# PCB_ROHM_BaAnh.net
KiCad netlist of a schematic drawn in EAGLE
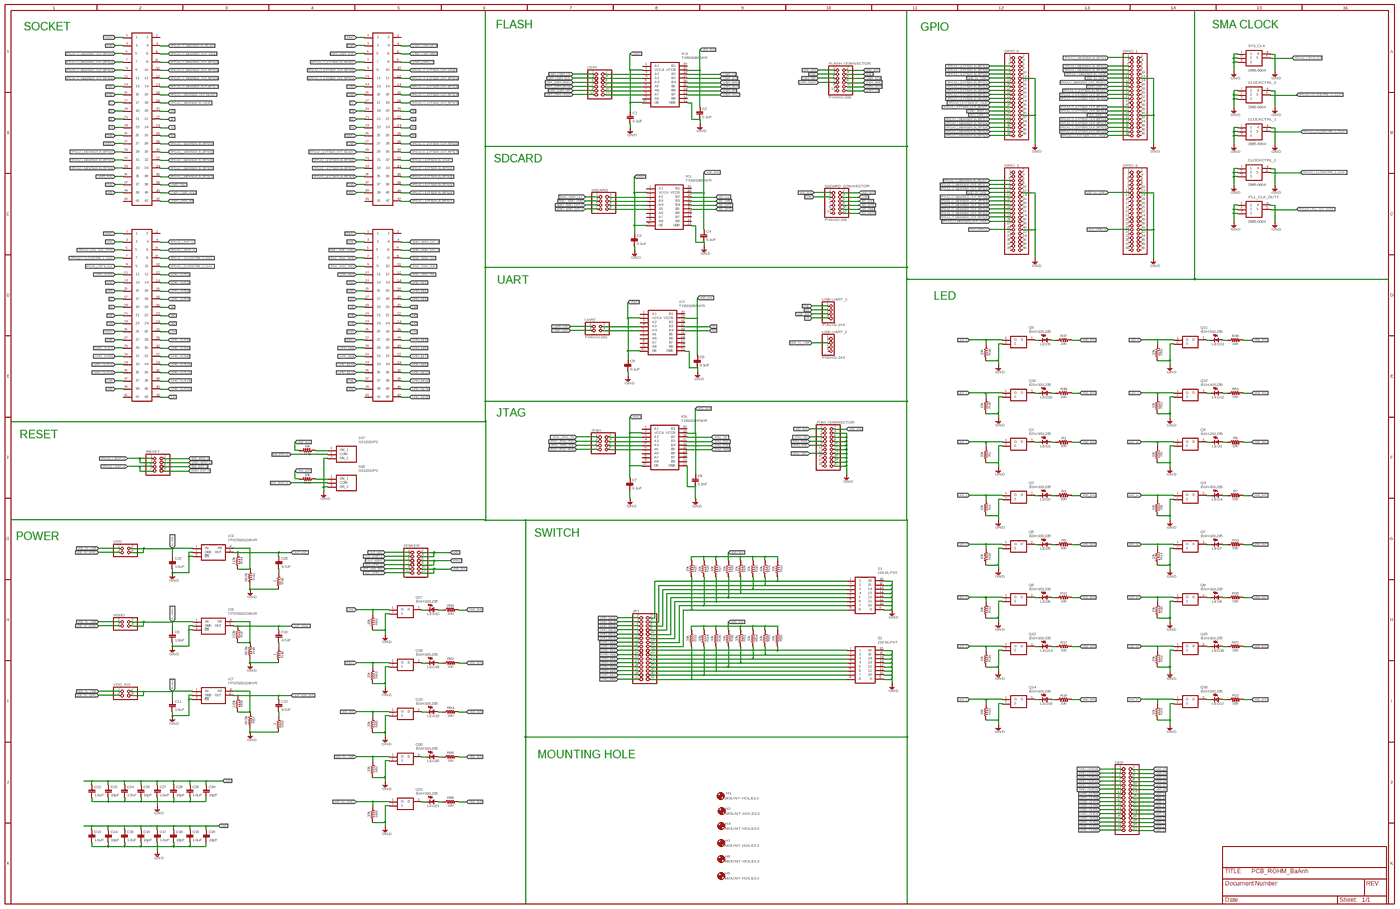
[diagram p0: schematic, sheet 1, overview]
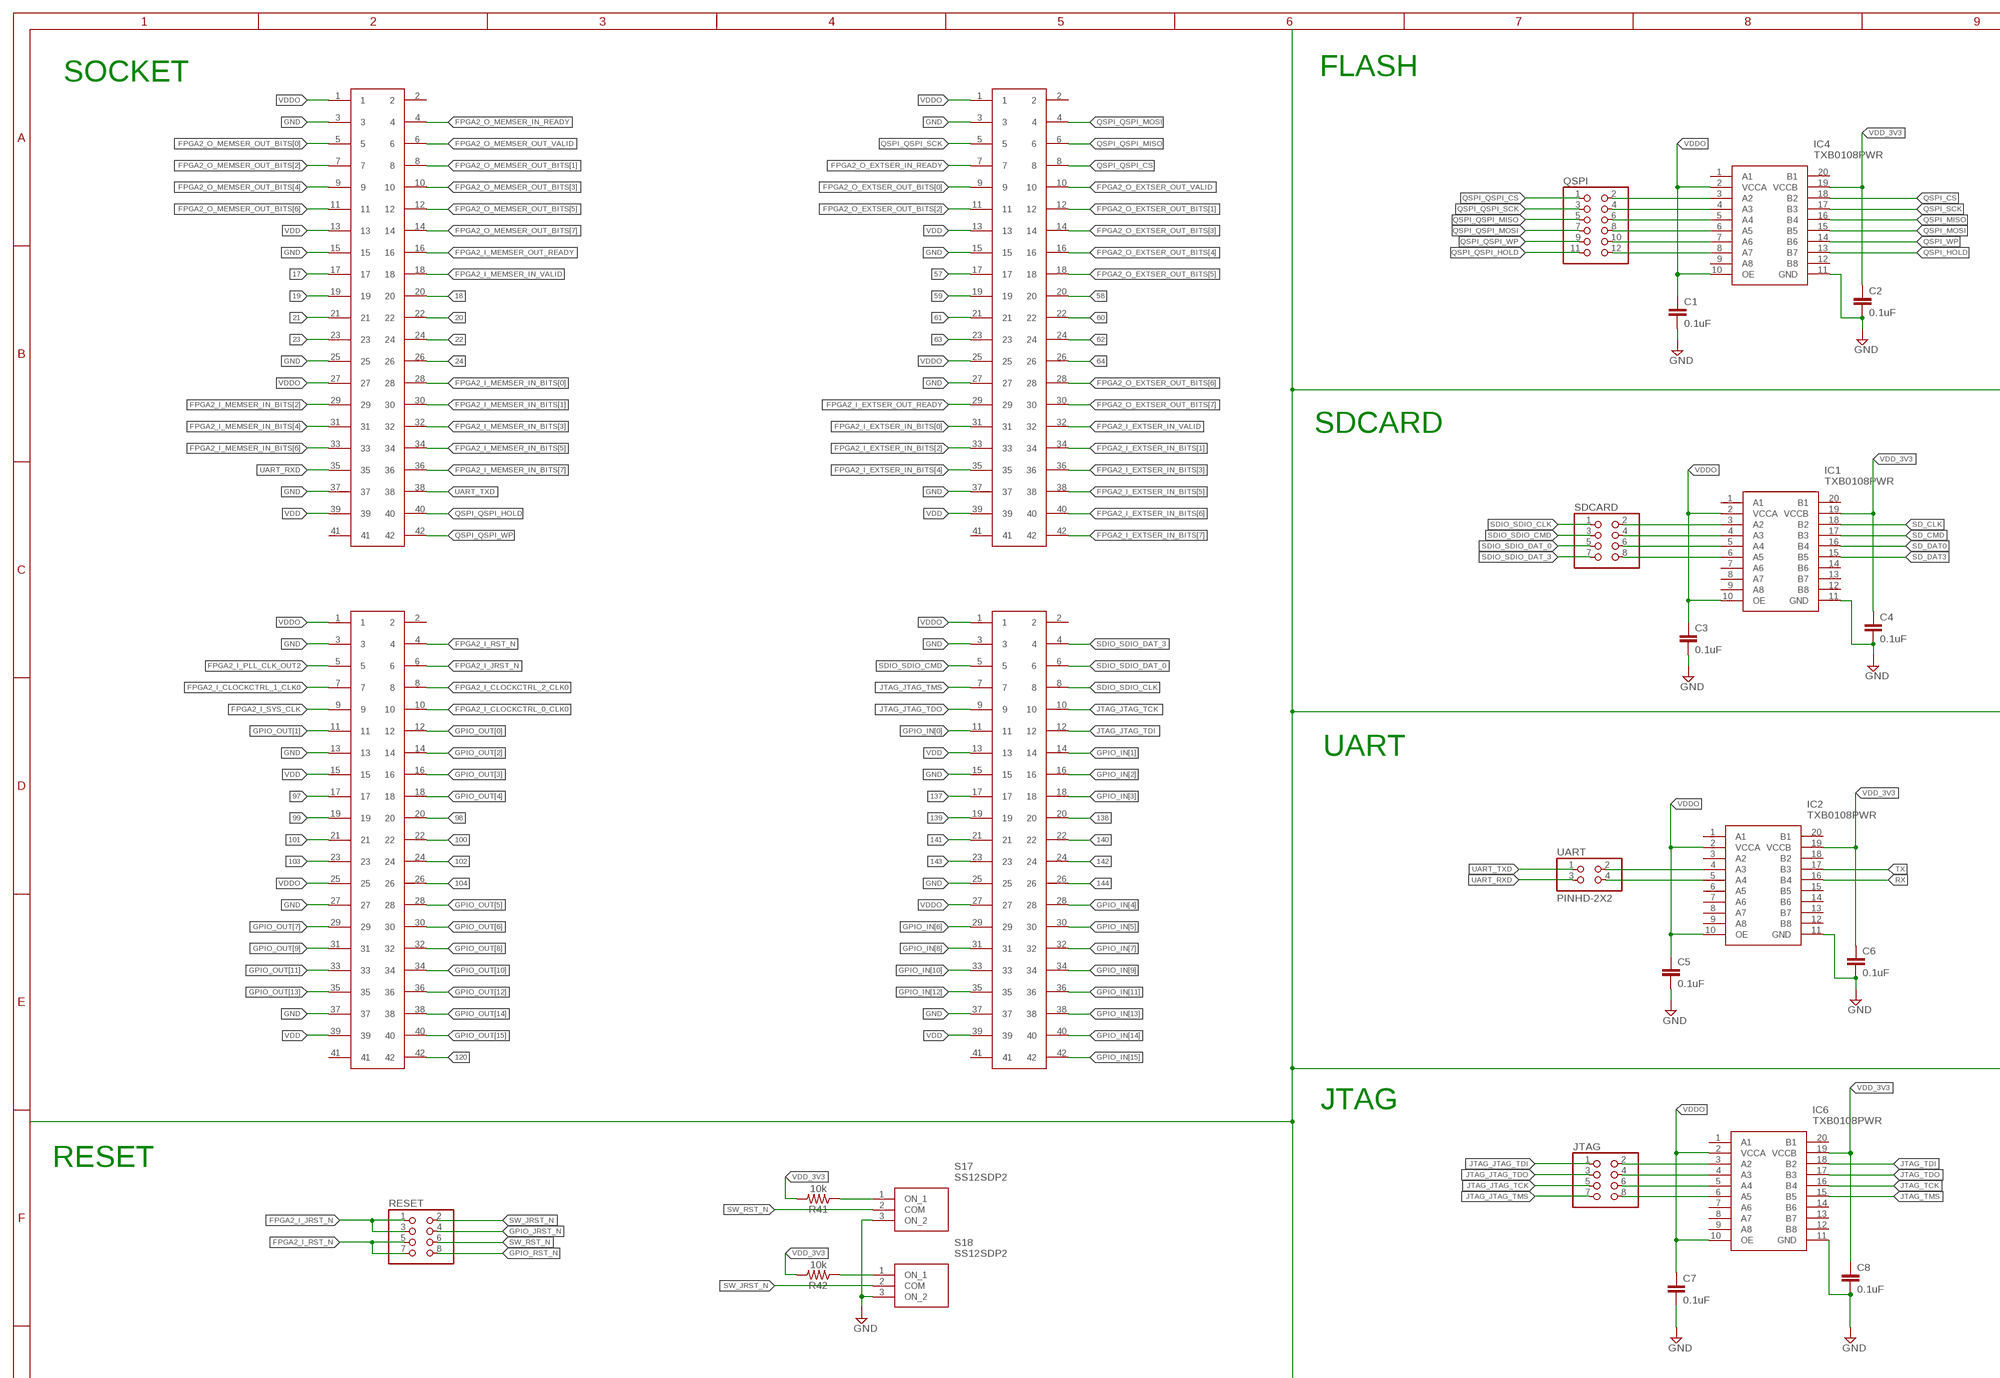
[diagram p1: schematic, sheet 1, part 1 of 4]
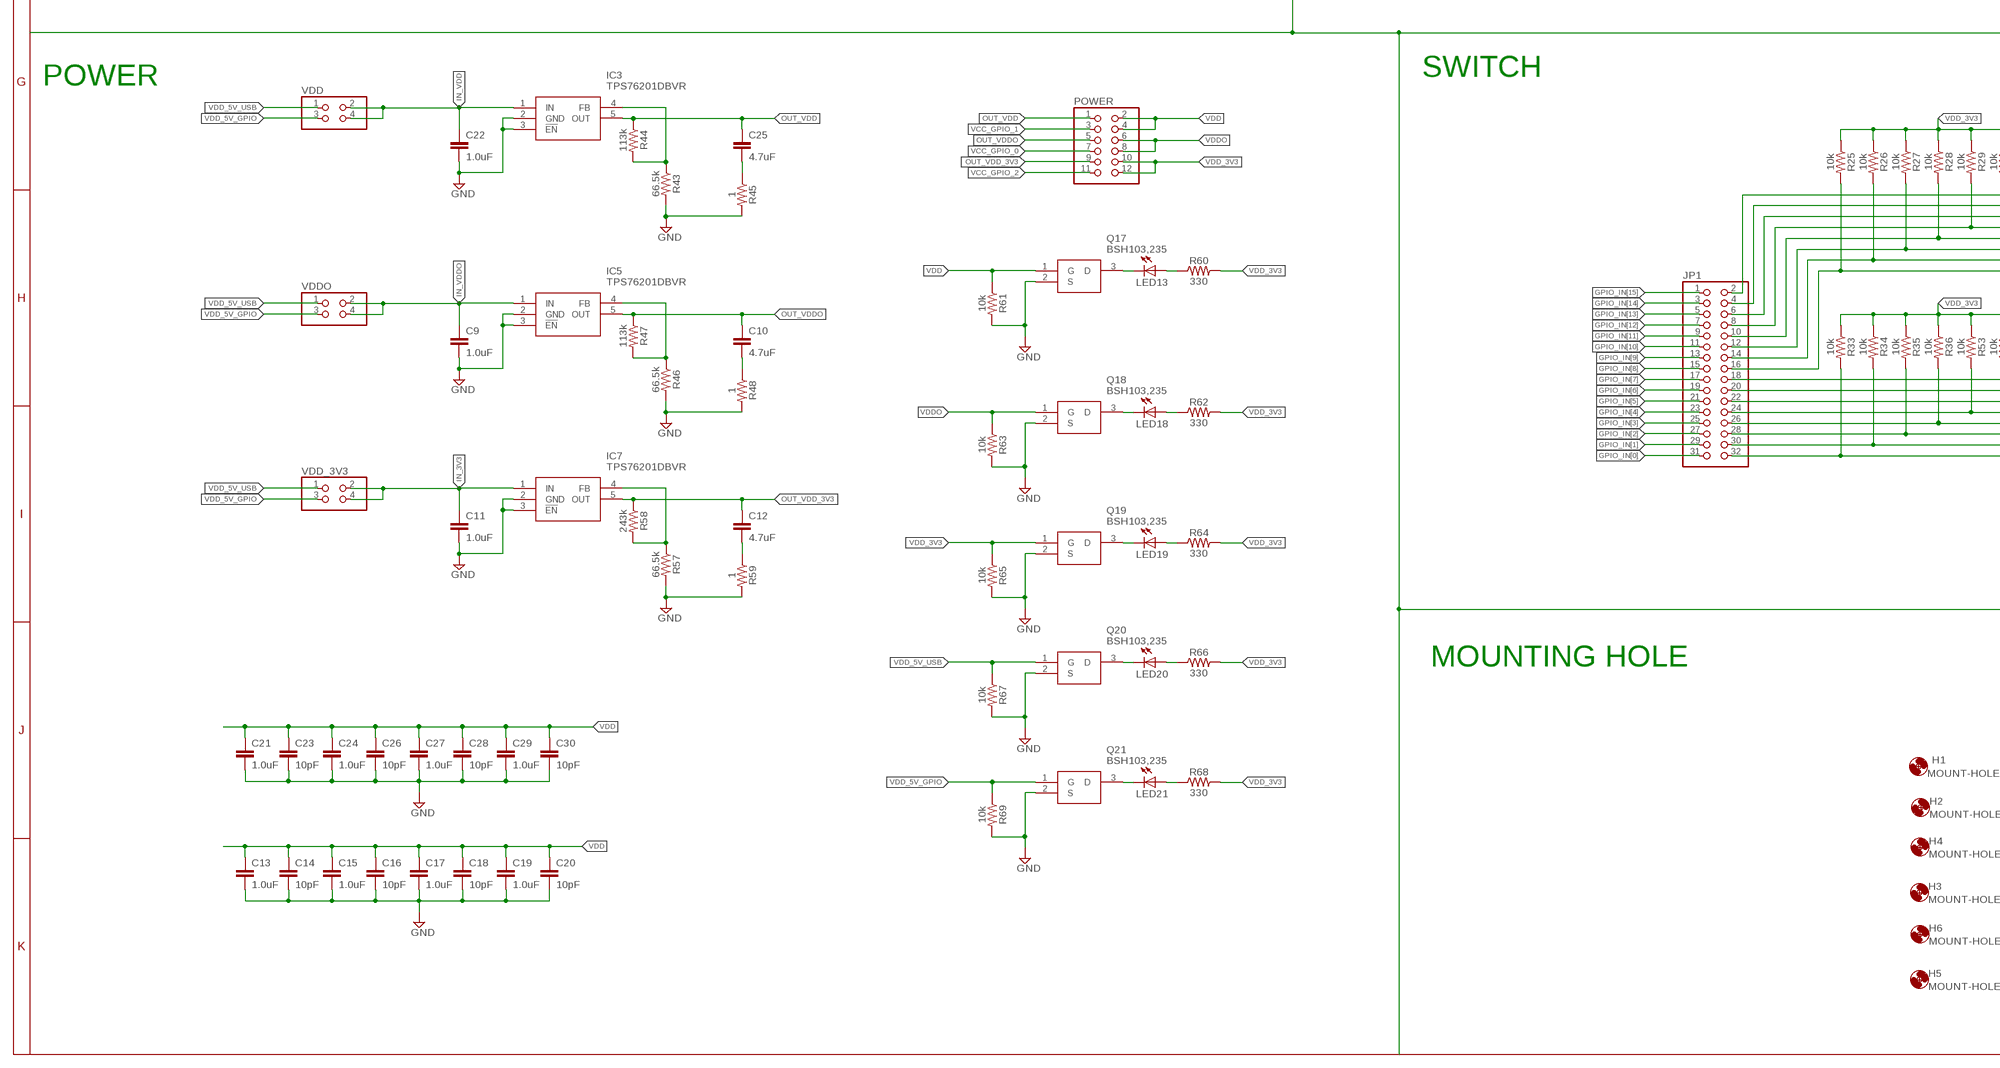
[diagram p2: schematic, sheet 1, part 2 of 4]
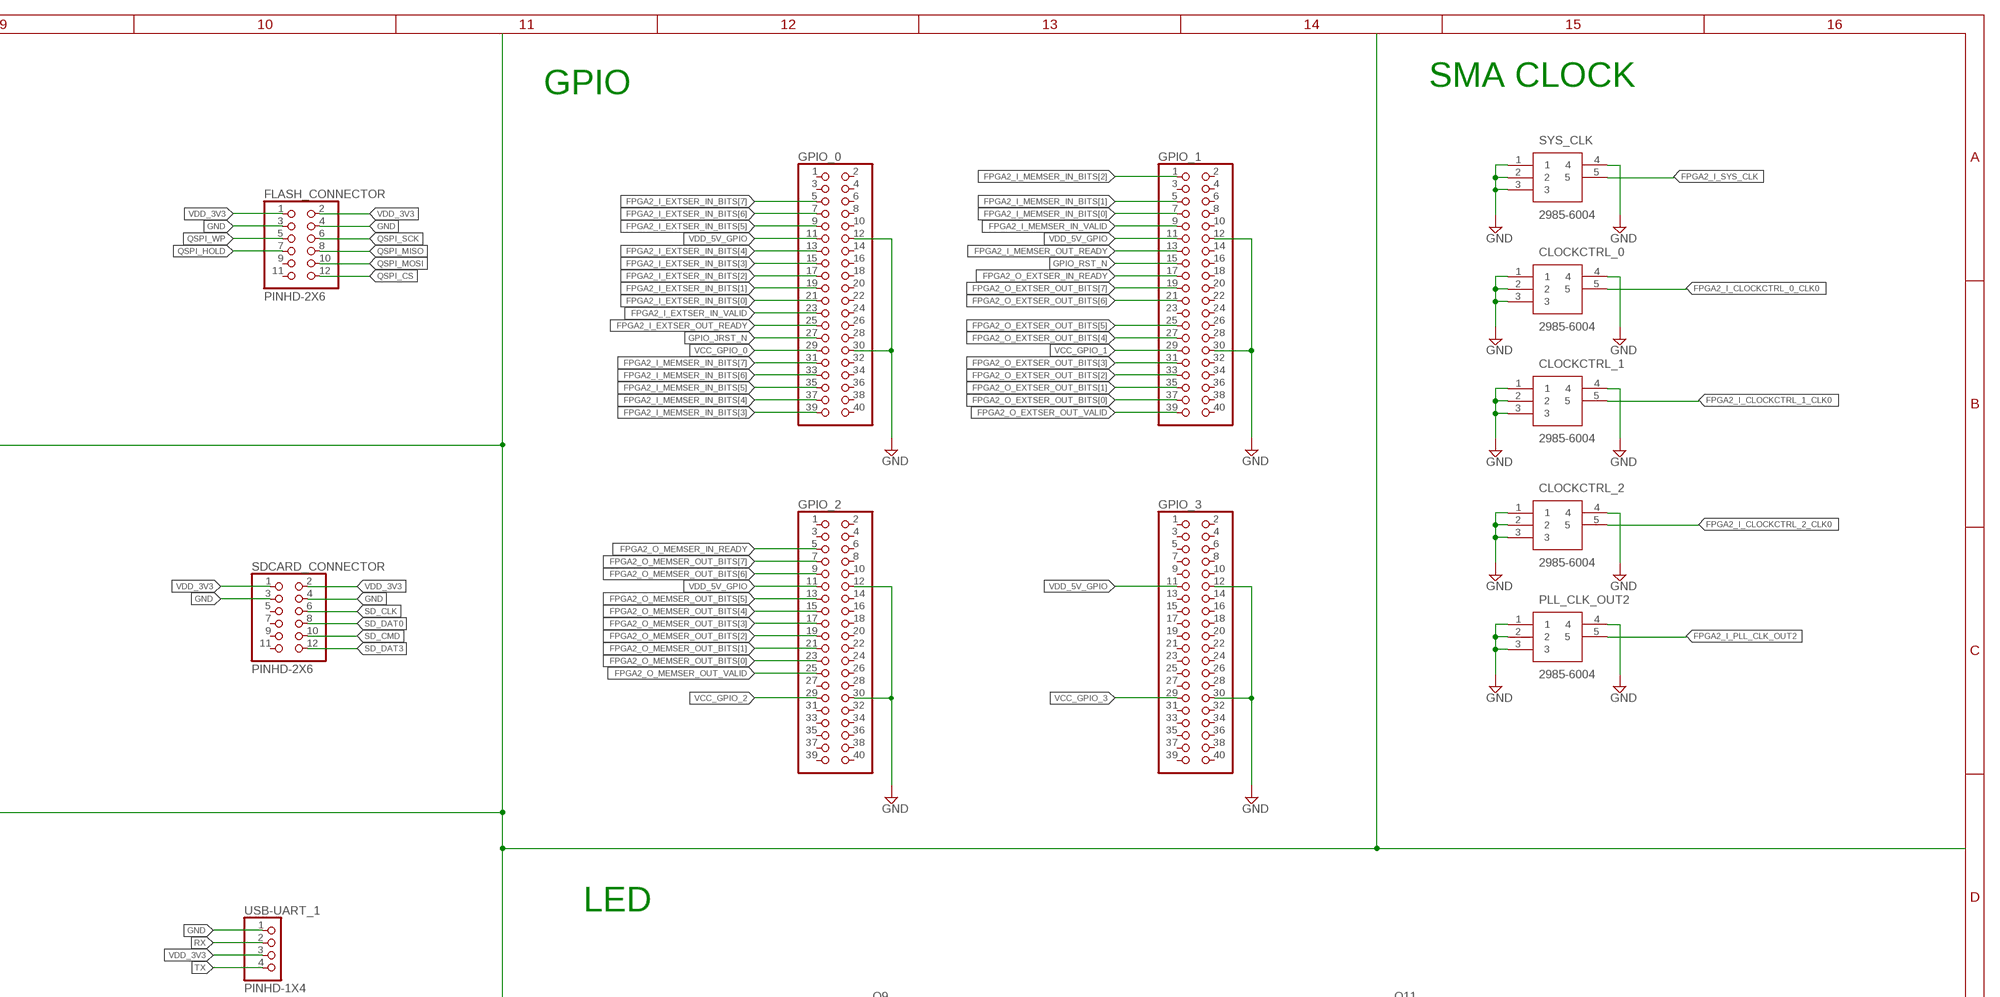
[diagram p3: schematic, sheet 1, part 3 of 4]
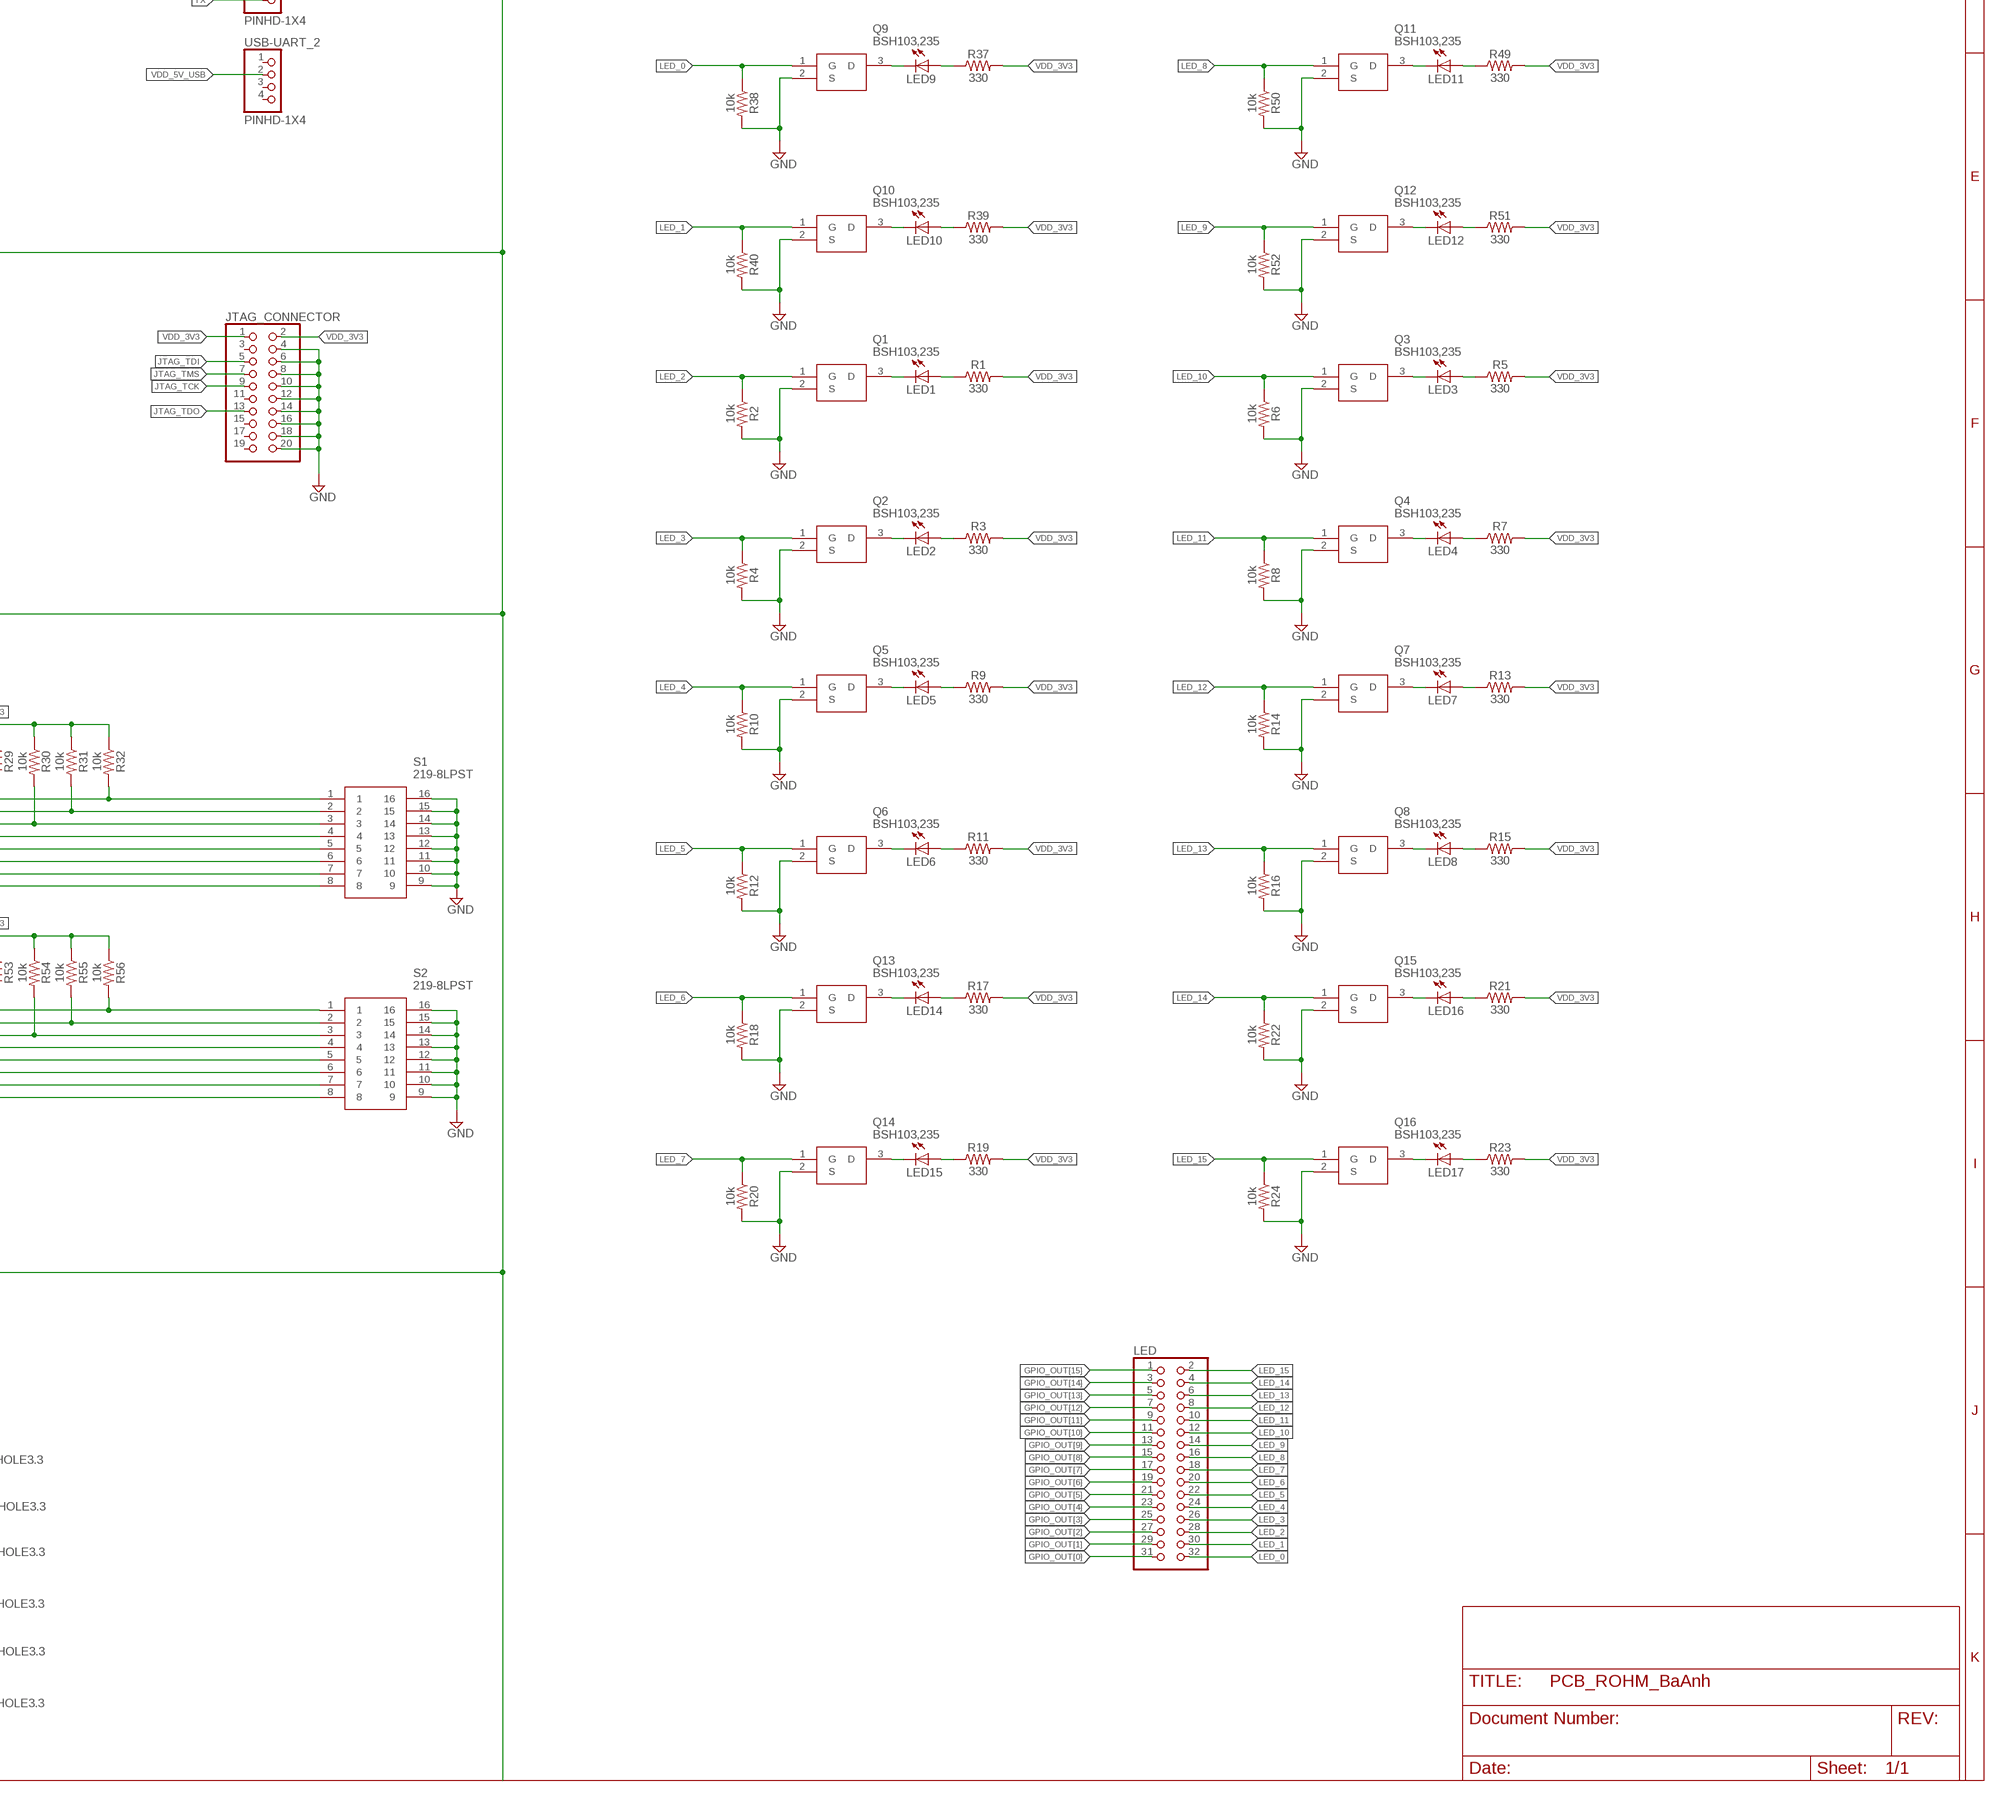
[diagram p4: schematic, sheet 1, part 4 of 4]

(export (version "E")
  (design (tool "Eeschema 10.0.6"))
  (components
    (comp (ref "C1")
      (value "0.1uF")
      (footprint "eagle-import:0805")
      (libsource (lib "eagle-import") (part "1.0UF-0805-25V-(+80/-20%)"))
    )
    (comp (ref "C2")
      (value "0.1uF")
      (footprint "eagle-import:0805")
      (libsource (lib "eagle-import") (part "1.0UF-0805-25V-(+80/-20%)"))
    )
    (comp (ref "C3")
      (value "0.1uF")
      (footprint "eagle-import:0805")
      (libsource (lib "eagle-import") (part "1.0UF-0805-25V-(+80/-20%)"))
    )
    (comp (ref "C4")
      (value "0.1uF")
      (footprint "eagle-import:0805")
      (libsource (lib "eagle-import") (part "1.0UF-0805-25V-(+80/-20%)"))
    )
    (comp (ref "C5")
      (value "0.1uF")
      (footprint "eagle-import:0805")
      (libsource (lib "eagle-import") (part "1.0UF-0805-25V-(+80/-20%)"))
    )
    (comp (ref "C6")
      (value "0.1uF")
      (footprint "eagle-import:0805")
      (libsource (lib "eagle-import") (part "1.0UF-0805-25V-(+80/-20%)"))
    )
    (comp (ref "C7")
      (value "0.1uF")
      (footprint "eagle-import:0805")
      (libsource (lib "eagle-import") (part "1.0UF-0805-25V-(+80/-20%)"))
    )
    (comp (ref "C8")
      (value "0.1uF")
      (footprint "eagle-import:0805")
      (libsource (lib "eagle-import") (part "1.0UF-0805-25V-(+80/-20%)"))
    )
    (comp (ref "C9")
      (value "1.0uF")
      (footprint "eagle-import:0805")
      (libsource (lib "eagle-import") (part "1.0UF-0805-25V-(+80/-20%)"))
    )
    (comp (ref "C10")
      (value "4.7uF")
      (footprint "eagle-import:0805")
      (libsource (lib "eagle-import") (part "1.0UF-0805-25V-(+80/-20%)"))
    )
    (comp (ref "C11")
      (value "1.0uF")
      (footprint "eagle-import:0805")
      (libsource (lib "eagle-import") (part "1.0UF-0805-25V-(+80/-20%)"))
    )
    (comp (ref "C12")
      (value "4.7uF")
      (footprint "eagle-import:0805")
      (libsource (lib "eagle-import") (part "1.0UF-0805-25V-(+80/-20%)"))
    )
    (comp (ref "C13")
      (value "1.0uF")
      (footprint "eagle-import:0805")
      (libsource (lib "eagle-import") (part "1.0UF-0805-25V-(+80/-20%)"))
    )
    (comp (ref "C14")
      (value "10pF")
      (footprint "eagle-import:0805")
      (libsource (lib "eagle-import") (part "1.0UF-0805-25V-(+80/-20%)"))
    )
    (comp (ref "C15")
      (value "1.0uF")
      (footprint "eagle-import:0805")
      (libsource (lib "eagle-import") (part "1.0UF-0805-25V-(+80/-20%)"))
    )
    (comp (ref "C16")
      (value "10pF")
      (footprint "eagle-import:0805")
      (libsource (lib "eagle-import") (part "1.0UF-0805-25V-(+80/-20%)"))
    )
    (comp (ref "C17")
      (value "1.0uF")
      (footprint "eagle-import:0805")
      (libsource (lib "eagle-import") (part "1.0UF-0805-25V-(+80/-20%)"))
    )
    (comp (ref "C18")
      (value "10pF")
      (footprint "eagle-import:0805")
      (libsource (lib "eagle-import") (part "1.0UF-0805-25V-(+80/-20%)"))
    )
    (comp (ref "C19")
      (value "1.0uF")
      (footprint "eagle-import:0805")
      (libsource (lib "eagle-import") (part "1.0UF-0805-25V-(+80/-20%)"))
    )
    (comp (ref "C20")
      (value "10pF")
      (footprint "eagle-import:0805")
      (libsource (lib "eagle-import") (part "1.0UF-0805-25V-(+80/-20%)"))
    )
    (comp (ref "C21")
      (value "1.0uF")
      (footprint "eagle-import:0805")
      (libsource (lib "eagle-import") (part "1.0UF-0805-25V-(+80/-20%)"))
    )
    (comp (ref "C22")
      (value "1.0uF")
      (footprint "eagle-import:0805")
      (libsource (lib "eagle-import") (part "1.0UF-0805-25V-(+80/-20%)"))
    )
    (comp (ref "C23")
      (value "10pF")
      (footprint "eagle-import:0805")
      (libsource (lib "eagle-import") (part "1.0UF-0805-25V-(+80/-20%)"))
    )
    (comp (ref "C24")
      (value "1.0uF")
      (footprint "eagle-import:0805")
      (libsource (lib "eagle-import") (part "1.0UF-0805-25V-(+80/-20%)"))
    )
    (comp (ref "C25")
      (value "4.7uF")
      (footprint "eagle-import:0805")
      (libsource (lib "eagle-import") (part "1.0UF-0805-25V-(+80/-20%)"))
    )
    (comp (ref "C26")
      (value "10pF")
      (footprint "eagle-import:0805")
      (libsource (lib "eagle-import") (part "1.0UF-0805-25V-(+80/-20%)"))
    )
    (comp (ref "C27")
      (value "1.0uF")
      (footprint "eagle-import:0805")
      (libsource (lib "eagle-import") (part "1.0UF-0805-25V-(+80/-20%)"))
    )
    (comp (ref "C28")
      (value "10pF")
      (footprint "eagle-import:0805")
      (libsource (lib "eagle-import") (part "1.0UF-0805-25V-(+80/-20%)"))
    )
    (comp (ref "C29")
      (value "1.0uF")
      (footprint "eagle-import:0805")
      (libsource (lib "eagle-import") (part "1.0UF-0805-25V-(+80/-20%)"))
    )
    (comp (ref "C30")
      (value "10pF")
      (footprint "eagle-import:0805")
      (libsource (lib "eagle-import") (part "1.0UF-0805-25V-(+80/-20%)"))
    )
    (comp (ref "CLOCKCTRL_0")
      (value "2985-6004")
      (footprint "eagle-import:29856004")
      (fields (field (name "MOUSER_PART_NUMBER") "523-2985-6004"))
      (libsource (lib "eagle-import") (part "2985-6004"))
    )
    (comp (ref "CLOCKCTRL_1")
      (value "2985-6004")
      (footprint "eagle-import:29856004")
      (fields (field (name "MOUSER_PART_NUMBER") "523-2985-6004"))
      (libsource (lib "eagle-import") (part "2985-6004"))
    )
    (comp (ref "CLOCKCTRL_2")
      (value "2985-6004")
      (footprint "eagle-import:29856004")
      (fields (field (name "MOUSER_PART_NUMBER") "523-2985-6004"))
      (libsource (lib "eagle-import") (part "2985-6004"))
    )
    (comp (ref "FLASH_CONNECTOR")
      (value "PINHD-2X6")
      (footprint "eagle-import:2X06")
      (libsource (lib "eagle-import") (part "PINHD-2X6"))
    )
    (comp (ref "GPIO_0")
      (value "PINHD-2X20")
      (footprint "eagle-import:2X20")
      (libsource (lib "eagle-import") (part "PINHD-2X20"))
    )
    (comp (ref "GPIO_1")
      (value "PINHD-2X20")
      (footprint "eagle-import:2X20")
      (libsource (lib "eagle-import") (part "PINHD-2X20"))
    )
    (comp (ref "GPIO_2")
      (value "PINHD-2X20")
      (footprint "eagle-import:2X20")
      (libsource (lib "eagle-import") (part "PINHD-2X20"))
    )
    (comp (ref "GPIO_3")
      (value "PINHD-2X20")
      (footprint "eagle-import:2X20")
      (libsource (lib "eagle-import") (part "PINHD-2X20"))
    )
    (comp (ref "H1")
      (value "MOUNT-HOLE3.3")
      (footprint "eagle-import:3,3")
      (libsource (lib "eagle-import") (part "MOUNT-HOLE3.3"))
    )
    (comp (ref "H2")
      (value "MOUNT-HOLE3.3")
      (footprint "eagle-import:3,3")
      (libsource (lib "eagle-import") (part "MOUNT-HOLE3.3"))
    )
    (comp (ref "H3")
      (value "MOUNT-HOLE3.3")
      (footprint "eagle-import:3,3")
      (libsource (lib "eagle-import") (part "MOUNT-HOLE3.3"))
    )
    (comp (ref "H4")
      (value "MOUNT-HOLE3.3")
      (footprint "eagle-import:3,3")
      (libsource (lib "eagle-import") (part "MOUNT-HOLE3.3"))
    )
    (comp (ref "H5")
      (value "MOUNT-HOLE3.3")
      (footprint "eagle-import:3,3")
      (libsource (lib "eagle-import") (part "MOUNT-HOLE3.3"))
    )
    (comp (ref "H6")
      (value "MOUNT-HOLE3.3")
      (footprint "eagle-import:3,3")
      (libsource (lib "eagle-import") (part "MOUNT-HOLE3.3"))
    )
    (comp (ref "IC1")
      (value "TXB0108PWR")
      (footprint "eagle-import:SOP65P640X120-20N")
      (fields (field (name "MOUSER_PART_NUMBER") "595-TXB0108PWR"))
      (libsource (lib "eagle-import") (part "TXB0108PWR"))
    )
    (comp (ref "IC2")
      (value "TXB0108PWR")
      (footprint "eagle-import:SOP65P640X120-20N")
      (fields (field (name "MOUSER_PART_NUMBER") "595-TXB0108PWR"))
      (libsource (lib "eagle-import") (part "TXB0108PWR"))
    )
    (comp (ref "IC3")
      (value "TPS76201DBVR")
      (footprint "eagle-import:SOT95P280X145-5N")
      (fields (field (name "MOUSER_PART_NUMBER") "595-TPS76201DBVR"))
      (libsource (lib "eagle-import") (part "TPS76201DBVR"))
    )
    (comp (ref "IC4")
      (value "TXB0108PWR")
      (footprint "eagle-import:SOP65P640X120-20N")
      (fields (field (name "MOUSER_PART_NUMBER") "595-TXB0108PWR"))
      (libsource (lib "eagle-import") (part "TXB0108PWR"))
    )
    (comp (ref "IC5")
      (value "TPS76201DBVR")
      (footprint "eagle-import:SOT95P280X145-5N")
      (fields (field (name "MOUSER_PART_NUMBER") "595-TPS76201DBVR"))
      (libsource (lib "eagle-import") (part "TPS76201DBVR"))
    )
    (comp (ref "IC6")
      (value "TXB0108PWR")
      (footprint "eagle-import:SOP65P640X120-20N")
      (fields (field (name "MOUSER_PART_NUMBER") "595-TXB0108PWR"))
      (libsource (lib "eagle-import") (part "TXB0108PWR"))
    )
    (comp (ref "IC7")
      (value "TPS76201DBVR")
      (footprint "eagle-import:SOT95P280X145-5N")
      (fields (field (name "MOUSER_PART_NUMBER") "595-TPS76201DBVR"))
      (libsource (lib "eagle-import") (part "TPS76201DBVR"))
    )
    (comp (ref "JP1")
      (value "PINHD-2X16")
      (footprint "eagle-import:2X16")
      (libsource (lib "eagle-import") (part "PINHD-2X16"))
    )
    (comp (ref "JTAG")
      (value "PINHD-2X4")
      (footprint "eagle-import:2X04")
      (libsource (lib "eagle-import") (part "PINHD-2X4"))
    )
    (comp (ref "JTAG_CONNECTOR")
      (value "PINHD-2X10")
      (footprint "eagle-import:2X10")
      (libsource (lib "eagle-import") (part "PINHD-2X10"))
    )
    (comp (ref "LED")
      (value "PINHD-2X16")
      (footprint "eagle-import:2X16")
      (libsource (lib "eagle-import") (part "PINHD-2X16"))
    )
    (comp (ref "LED1")
      (value "LEDCHIP-LED0805")
      (footprint "eagle-import:CHIP-LED0805")
      (libsource (lib "eagle-import") (part "LEDCHIP-LED0805"))
    )
    (comp (ref "LED2")
      (value "LEDCHIP-LED0805")
      (footprint "eagle-import:CHIP-LED0805")
      (libsource (lib "eagle-import") (part "LEDCHIP-LED0805"))
    )
    (comp (ref "LED3")
      (value "LEDCHIP-LED0805")
      (footprint "eagle-import:CHIP-LED0805")
      (libsource (lib "eagle-import") (part "LEDCHIP-LED0805"))
    )
    (comp (ref "LED4")
      (value "LEDCHIP-LED0805")
      (footprint "eagle-import:CHIP-LED0805")
      (libsource (lib "eagle-import") (part "LEDCHIP-LED0805"))
    )
    (comp (ref "LED5")
      (value "LEDCHIP-LED0805")
      (footprint "eagle-import:CHIP-LED0805")
      (libsource (lib "eagle-import") (part "LEDCHIP-LED0805"))
    )
    (comp (ref "LED6")
      (value "LEDCHIP-LED0805")
      (footprint "eagle-import:CHIP-LED0805")
      (libsource (lib "eagle-import") (part "LEDCHIP-LED0805"))
    )
    (comp (ref "LED7")
      (value "LEDCHIP-LED0805")
      (footprint "eagle-import:CHIP-LED0805")
      (libsource (lib "eagle-import") (part "LEDCHIP-LED0805"))
    )
    (comp (ref "LED8")
      (value "LEDCHIP-LED0805")
      (footprint "eagle-import:CHIP-LED0805")
      (libsource (lib "eagle-import") (part "LEDCHIP-LED0805"))
    )
    (comp (ref "LED9")
      (value "LEDCHIP-LED0805")
      (footprint "eagle-import:CHIP-LED0805")
      (libsource (lib "eagle-import") (part "LEDCHIP-LED0805"))
    )
    (comp (ref "LED10")
      (value "LEDCHIP-LED0805")
      (footprint "eagle-import:CHIP-LED0805")
      (libsource (lib "eagle-import") (part "LEDCHIP-LED0805"))
    )
    (comp (ref "LED11")
      (value "LEDCHIP-LED0805")
      (footprint "eagle-import:CHIP-LED0805")
      (libsource (lib "eagle-import") (part "LEDCHIP-LED0805"))
    )
    (comp (ref "LED12")
      (value "LEDCHIP-LED0805")
      (footprint "eagle-import:CHIP-LED0805")
      (libsource (lib "eagle-import") (part "LEDCHIP-LED0805"))
    )
    (comp (ref "LED13")
      (value "LEDCHIP-LED0805")
      (footprint "eagle-import:CHIP-LED0805")
      (libsource (lib "eagle-import") (part "LEDCHIP-LED0805"))
    )
    (comp (ref "LED14")
      (value "LEDCHIP-LED0805")
      (footprint "eagle-import:CHIP-LED0805")
      (libsource (lib "eagle-import") (part "LEDCHIP-LED0805"))
    )
    (comp (ref "LED15")
      (value "LEDCHIP-LED0805")
      (footprint "eagle-import:CHIP-LED0805")
      (libsource (lib "eagle-import") (part "LEDCHIP-LED0805"))
    )
    (comp (ref "LED16")
      (value "LEDCHIP-LED0805")
      (footprint "eagle-import:CHIP-LED0805")
      (libsource (lib "eagle-import") (part "LEDCHIP-LED0805"))
    )
    (comp (ref "LED17")
      (value "LEDCHIP-LED0805")
      (footprint "eagle-import:CHIP-LED0805")
      (libsource (lib "eagle-import") (part "LEDCHIP-LED0805"))
    )
    (comp (ref "LED18")
      (value "LEDCHIP-LED0805")
      (footprint "eagle-import:CHIP-LED0805")
      (libsource (lib "eagle-import") (part "LEDCHIP-LED0805"))
    )
    (comp (ref "LED19")
      (value "LEDCHIP-LED0805")
      (footprint "eagle-import:CHIP-LED0805")
      (libsource (lib "eagle-import") (part "LEDCHIP-LED0805"))
    )
    (comp (ref "LED20")
      (value "LEDCHIP-LED0805")
      (footprint "eagle-import:CHIP-LED0805")
      (libsource (lib "eagle-import") (part "LEDCHIP-LED0805"))
    )
    (comp (ref "LED21")
      (value "LEDCHIP-LED0805")
      (footprint "eagle-import:CHIP-LED0805")
      (libsource (lib "eagle-import") (part "LEDCHIP-LED0805"))
    )
    (comp (ref "PLL_CLK_OUT2")
      (value "2985-6004")
      (footprint "eagle-import:29856004")
      (fields (field (name "MOUSER_PART_NUMBER") "523-2985-6004"))
      (libsource (lib "eagle-import") (part "2985-6004"))
    )
    (comp (ref "POWER")
      (value "PINHD-2X6")
      (footprint "eagle-import:2X06")
      (libsource (lib "eagle-import") (part "pinhead_325_PINHD-2X6"))
    )
    (comp (ref "Q1")
      (value "BSH103,235")
      (footprint "eagle-import:SOT95P230X110-3N")
      (fields (field (name "MOUSER_PART_NUMBER") "771-BSH103235"))
      (libsource (lib "eagle-import") (part "BSH103,235"))
    )
    (comp (ref "Q2")
      (value "BSH103,235")
      (footprint "eagle-import:SOT95P230X110-3N")
      (fields (field (name "MOUSER_PART_NUMBER") "771-BSH103235"))
      (libsource (lib "eagle-import") (part "BSH103,235"))
    )
    (comp (ref "Q3")
      (value "BSH103,235")
      (footprint "eagle-import:SOT95P230X110-3N")
      (fields (field (name "MOUSER_PART_NUMBER") "771-BSH103235"))
      (libsource (lib "eagle-import") (part "BSH103,235"))
    )
    (comp (ref "Q4")
      (value "BSH103,235")
      (footprint "eagle-import:SOT95P230X110-3N")
      (fields (field (name "MOUSER_PART_NUMBER") "771-BSH103235"))
      (libsource (lib "eagle-import") (part "BSH103,235"))
    )
    (comp (ref "Q5")
      (value "BSH103,235")
      (footprint "eagle-import:SOT95P230X110-3N")
      (fields (field (name "MOUSER_PART_NUMBER") "771-BSH103235"))
      (libsource (lib "eagle-import") (part "BSH103,235"))
    )
    (comp (ref "Q6")
      (value "BSH103,235")
      (footprint "eagle-import:SOT95P230X110-3N")
      (fields (field (name "MOUSER_PART_NUMBER") "771-BSH103235"))
      (libsource (lib "eagle-import") (part "BSH103,235"))
    )
    (comp (ref "Q7")
      (value "BSH103,235")
      (footprint "eagle-import:SOT95P230X110-3N")
      (fields (field (name "MOUSER_PART_NUMBER") "771-BSH103235"))
      (libsource (lib "eagle-import") (part "BSH103,235"))
    )
    (comp (ref "Q8")
      (value "BSH103,235")
      (footprint "eagle-import:SOT95P230X110-3N")
      (fields (field (name "MOUSER_PART_NUMBER") "771-BSH103235"))
      (libsource (lib "eagle-import") (part "BSH103,235"))
    )
    (comp (ref "Q9")
      (value "BSH103,235")
      (footprint "eagle-import:SOT95P230X110-3N")
      (fields (field (name "MOUSER_PART_NUMBER") "771-BSH103235"))
      (libsource (lib "eagle-import") (part "BSH103,235"))
    )
    (comp (ref "Q10")
      (value "BSH103,235")
      (footprint "eagle-import:SOT95P230X110-3N")
      (fields (field (name "MOUSER_PART_NUMBER") "771-BSH103235"))
      (libsource (lib "eagle-import") (part "BSH103,235"))
    )
    (comp (ref "Q11")
      (value "BSH103,235")
      (footprint "eagle-import:SOT95P230X110-3N")
      (fields (field (name "MOUSER_PART_NUMBER") "771-BSH103235"))
      (libsource (lib "eagle-import") (part "BSH103,235"))
    )
    (comp (ref "Q12")
      (value "BSH103,235")
      (footprint "eagle-import:SOT95P230X110-3N")
      (fields (field (name "MOUSER_PART_NUMBER") "771-BSH103235"))
      (libsource (lib "eagle-import") (part "BSH103,235"))
    )
    (comp (ref "Q13")
      (value "BSH103,235")
      (footprint "eagle-import:SOT95P230X110-3N")
      (fields (field (name "MOUSER_PART_NUMBER") "771-BSH103235"))
      (libsource (lib "eagle-import") (part "BSH103,235"))
    )
    (comp (ref "Q14")
      (value "BSH103,235")
      (footprint "eagle-import:SOT95P230X110-3N")
      (fields (field (name "MOUSER_PART_NUMBER") "771-BSH103235"))
      (libsource (lib "eagle-import") (part "BSH103,235"))
    )
    (comp (ref "Q15")
      (value "BSH103,235")
      (footprint "eagle-import:SOT95P230X110-3N")
      (fields (field (name "MOUSER_PART_NUMBER") "771-BSH103235"))
      (libsource (lib "eagle-import") (part "BSH103,235"))
    )
    (comp (ref "Q16")
      (value "BSH103,235")
      (footprint "eagle-import:SOT95P230X110-3N")
      (fields (field (name "MOUSER_PART_NUMBER") "771-BSH103235"))
      (libsource (lib "eagle-import") (part "BSH103,235"))
    )
    (comp (ref "Q17")
      (value "BSH103,235")
      (footprint "eagle-import:SOT95P230X110-3N")
      (fields (field (name "MOUSER_PART_NUMBER") "771-BSH103235"))
      (libsource (lib "eagle-import") (part "BSH103,235"))
    )
    (comp (ref "Q18")
      (value "BSH103,235")
      (footprint "eagle-import:SOT95P230X110-3N")
      (fields (field (name "MOUSER_PART_NUMBER") "771-BSH103235"))
      (libsource (lib "eagle-import") (part "BSH103,235"))
    )
    (comp (ref "Q19")
      (value "BSH103,235")
      (footprint "eagle-import:SOT95P230X110-3N")
      (fields (field (name "MOUSER_PART_NUMBER") "771-BSH103235"))
      (libsource (lib "eagle-import") (part "BSH103,235"))
    )
    (comp (ref "Q20")
      (value "BSH103,235")
      (footprint "eagle-import:SOT95P230X110-3N")
      (fields (field (name "MOUSER_PART_NUMBER") "771-BSH103235"))
      (libsource (lib "eagle-import") (part "BSH103,235"))
    )
    (comp (ref "Q21")
      (value "BSH103,235")
      (footprint "eagle-import:SOT95P230X110-3N")
      (fields (field (name "MOUSER_PART_NUMBER") "771-BSH103235"))
      (libsource (lib "eagle-import") (part "BSH103,235"))
    )
    (comp (ref "QSPI")
      (value "PINHD-2X6")
      (footprint "eagle-import:2X06")
      (libsource (lib "eagle-import") (part "pinhead_325_PINHD-2X6"))
    )
    (comp (ref "R1")
      (value "330")
      (footprint "eagle-import:0805")
      (libsource (lib "eagle-import") (part "0.3OHM-0805-1/8W-1%"))
    )
    (comp (ref "R2")
      (value "10k")
      (footprint "eagle-import:0805")
      (libsource (lib "eagle-import") (part "0.3OHM-0805-1/8W-1%"))
    )
    (comp (ref "R3")
      (value "330")
      (footprint "eagle-import:0805")
      (libsource (lib "eagle-import") (part "0.3OHM-0805-1/8W-1%"))
    )
    (comp (ref "R4")
      (value "10k")
      (footprint "eagle-import:0805")
      (libsource (lib "eagle-import") (part "0.3OHM-0805-1/8W-1%"))
    )
    (comp (ref "R5")
      (value "330")
      (footprint "eagle-import:0805")
      (libsource (lib "eagle-import") (part "0.3OHM-0805-1/8W-1%"))
    )
    (comp (ref "R6")
      (value "10k")
      (footprint "eagle-import:0805")
      (libsource (lib "eagle-import") (part "0.3OHM-0805-1/8W-1%"))
    )
    (comp (ref "R7")
      (value "330")
      (footprint "eagle-import:0805")
      (libsource (lib "eagle-import") (part "0.3OHM-0805-1/8W-1%"))
    )
    (comp (ref "R8")
      (value "10k")
      (footprint "eagle-import:0805")
      (libsource (lib "eagle-import") (part "0.3OHM-0805-1/8W-1%"))
    )
    (comp (ref "R9")
      (value "330")
      (footprint "eagle-import:0805")
      (libsource (lib "eagle-import") (part "0.3OHM-0805-1/8W-1%"))
    )
    (comp (ref "R10")
      (value "10k")
      (footprint "eagle-import:0805")
      (libsource (lib "eagle-import") (part "0.3OHM-0805-1/8W-1%"))
    )
    (comp (ref "R11")
      (value "330")
      (footprint "eagle-import:0805")
      (libsource (lib "eagle-import") (part "0.3OHM-0805-1/8W-1%"))
    )
    (comp (ref "R12")
      (value "10k")
      (footprint "eagle-import:0805")
      (libsource (lib "eagle-import") (part "0.3OHM-0805-1/8W-1%"))
    )
    (comp (ref "R13")
      (value "330")
      (footprint "eagle-import:0805")
      (libsource (lib "eagle-import") (part "0.3OHM-0805-1/8W-1%"))
    )
    (comp (ref "R14")
      (value "10k")
      (footprint "eagle-import:0805")
      (libsource (lib "eagle-import") (part "0.3OHM-0805-1/8W-1%"))
    )
    (comp (ref "R15")
      (value "330")
      (footprint "eagle-import:0805")
      (libsource (lib "eagle-import") (part "0.3OHM-0805-1/8W-1%"))
    )
    (comp (ref "R16")
      (value "10k")
      (footprint "eagle-import:0805")
      (libsource (lib "eagle-import") (part "0.3OHM-0805-1/8W-1%"))
    )
    (comp (ref "R17")
      (value "330")
      (footprint "eagle-import:0805")
      (libsource (lib "eagle-import") (part "0.3OHM-0805-1/8W-1%"))
    )
    (comp (ref "R18")
      (value "10k")
      (footprint "eagle-import:0805")
      (libsource (lib "eagle-import") (part "0.3OHM-0805-1/8W-1%"))
    )
    (comp (ref "R19")
      (value "330")
      (footprint "eagle-import:0805")
      (libsource (lib "eagle-import") (part "0.3OHM-0805-1/8W-1%"))
    )
    (comp (ref "R20")
      (value "10k")
      (footprint "eagle-import:0805")
      (libsource (lib "eagle-import") (part "0.3OHM-0805-1/8W-1%"))
    )
    (comp (ref "R21")
      (value "330")
      (footprint "eagle-import:0805")
      (libsource (lib "eagle-import") (part "0.3OHM-0805-1/8W-1%"))
    )
    (comp (ref "R22")
      (value "10k")
      (footprint "eagle-import:0805")
      (libsource (lib "eagle-import") (part "0.3OHM-0805-1/8W-1%"))
    )
    (comp (ref "R23")
      (value "330")
      (footprint "eagle-import:0805")
      (libsource (lib "eagle-import") (part "0.3OHM-0805-1/8W-1%"))
    )
    (comp (ref "R24")
      (value "10k")
      (footprint "eagle-import:0805")
      (libsource (lib "eagle-import") (part "0.3OHM-0805-1/8W-1%"))
    )
    (comp (ref "R25")
      (value "10k")
      (footprint "eagle-import:0805")
      (libsource (lib "eagle-import") (part "0.3OHM-0805-1/8W-1%"))
    )
    (comp (ref "R26")
      (value "10k")
      (footprint "eagle-import:0805")
      (libsource (lib "eagle-import") (part "0.3OHM-0805-1/8W-1%"))
    )
    (comp (ref "R27")
      (value "10k")
      (footprint "eagle-import:0805")
      (libsource (lib "eagle-import") (part "0.3OHM-0805-1/8W-1%"))
    )
    (comp (ref "R28")
      (value "10k")
      (footprint "eagle-import:0805")
      (libsource (lib "eagle-import") (part "0.3OHM-0805-1/8W-1%"))
    )
    (comp (ref "R29")
      (value "10k")
      (footprint "eagle-import:0805")
      (libsource (lib "eagle-import") (part "0.3OHM-0805-1/8W-1%"))
    )
    (comp (ref "R30")
      (value "10k")
      (footprint "eagle-import:0805")
      (libsource (lib "eagle-import") (part "0.3OHM-0805-1/8W-1%"))
    )
    (comp (ref "R31")
      (value "10k")
      (footprint "eagle-import:0805")
      (libsource (lib "eagle-import") (part "0.3OHM-0805-1/8W-1%"))
    )
    (comp (ref "R32")
      (value "10k")
      (footprint "eagle-import:0805")
      (libsource (lib "eagle-import") (part "0.3OHM-0805-1/8W-1%"))
    )
    (comp (ref "R33")
      (value "10k")
      (footprint "eagle-import:0805")
      (libsource (lib "eagle-import") (part "0.3OHM-0805-1/8W-1%"))
    )
    (comp (ref "R34")
      (value "10k")
      (footprint "eagle-import:0805")
      (libsource (lib "eagle-import") (part "0.3OHM-0805-1/8W-1%"))
    )
    (comp (ref "R35")
      (value "10k")
      (footprint "eagle-import:0805")
      (libsource (lib "eagle-import") (part "0.3OHM-0805-1/8W-1%"))
    )
    (comp (ref "R36")
      (value "10k")
      (footprint "eagle-import:0805")
      (libsource (lib "eagle-import") (part "0.3OHM-0805-1/8W-1%"))
    )
    (comp (ref "R37")
      (value "330")
      (footprint "eagle-import:0805")
      (libsource (lib "eagle-import") (part "0.3OHM-0805-1/8W-1%"))
    )
    (comp (ref "R38")
      (value "10k")
      (footprint "eagle-import:0805")
      (libsource (lib "eagle-import") (part "0.3OHM-0805-1/8W-1%"))
    )
    (comp (ref "R39")
      (value "330")
      (footprint "eagle-import:0805")
      (libsource (lib "eagle-import") (part "0.3OHM-0805-1/8W-1%"))
    )
    (comp (ref "R40")
      (value "10k")
      (footprint "eagle-import:0805")
      (libsource (lib "eagle-import") (part "0.3OHM-0805-1/8W-1%"))
    )
    (comp (ref "R41")
      (value "10k")
      (footprint "eagle-import:0805")
      (libsource (lib "eagle-import") (part "0.3OHM-0805-1/8W-1%"))
    )
    (comp (ref "R42")
      (value "10k")
      (footprint "eagle-import:0805")
      (libsource (lib "eagle-import") (part "0.3OHM-0805-1/8W-1%"))
    )
    (comp (ref "R43")
      (value "66.5k")
      (footprint "eagle-import:0805")
      (libsource (lib "eagle-import") (part "0.3OHM-0805-1/8W-1%"))
    )
    (comp (ref "R44")
      (value "113k")
      (footprint "eagle-import:0805")
      (libsource (lib "eagle-import") (part "0.3OHM-0805-1/8W-1%"))
    )
    (comp (ref "R45")
      (value "1")
      (footprint "eagle-import:0805")
      (libsource (lib "eagle-import") (part "0.3OHM-0805-1/8W-1%"))
    )
    (comp (ref "R46")
      (value "66.5k")
      (footprint "eagle-import:0805")
      (libsource (lib "eagle-import") (part "0.3OHM-0805-1/8W-1%"))
    )
    (comp (ref "R47")
      (value "113k")
      (footprint "eagle-import:0805")
      (libsource (lib "eagle-import") (part "0.3OHM-0805-1/8W-1%"))
    )
    (comp (ref "R48")
      (value "1")
      (footprint "eagle-import:0805")
      (libsource (lib "eagle-import") (part "0.3OHM-0805-1/8W-1%"))
    )
    (comp (ref "R49")
      (value "330")
      (footprint "eagle-import:0805")
      (libsource (lib "eagle-import") (part "0.3OHM-0805-1/8W-1%"))
    )
    (comp (ref "R50")
      (value "10k")
      (footprint "eagle-import:0805")
      (libsource (lib "eagle-import") (part "0.3OHM-0805-1/8W-1%"))
    )
    (comp (ref "R51")
      (value "330")
      (footprint "eagle-import:0805")
      (libsource (lib "eagle-import") (part "0.3OHM-0805-1/8W-1%"))
    )
    (comp (ref "R52")
      (value "10k")
      (footprint "eagle-import:0805")
      (libsource (lib "eagle-import") (part "0.3OHM-0805-1/8W-1%"))
    )
    (comp (ref "R53")
      (value "10k")
      (footprint "eagle-import:0805")
      (libsource (lib "eagle-import") (part "0.3OHM-0805-1/8W-1%"))
    )
    (comp (ref "R54")
      (value "10k")
      (footprint "eagle-import:0805")
      (libsource (lib "eagle-import") (part "0.3OHM-0805-1/8W-1%"))
    )
    (comp (ref "R55")
      (value "10k")
      (footprint "eagle-import:0805")
      (libsource (lib "eagle-import") (part "0.3OHM-0805-1/8W-1%"))
    )
    (comp (ref "R56")
      (value "10k")
      (footprint "eagle-import:0805")
      (libsource (lib "eagle-import") (part "0.3OHM-0805-1/8W-1%"))
    )
    (comp (ref "R57")
      (value "66.5k")
      (footprint "eagle-import:0805")
      (libsource (lib "eagle-import") (part "0.3OHM-0805-1/8W-1%"))
    )
    (comp (ref "R58")
      (value "243k")
      (footprint "eagle-import:0805")
      (libsource (lib "eagle-import") (part "0.3OHM-0805-1/8W-1%"))
    )
    (comp (ref "R59")
      (value "1")
      (footprint "eagle-import:0805")
      (libsource (lib "eagle-import") (part "0.3OHM-0805-1/8W-1%"))
    )
    (comp (ref "R60")
      (value "330")
      (footprint "eagle-import:0805")
      (libsource (lib "eagle-import") (part "0.3OHM-0805-1/8W-1%"))
    )
    (comp (ref "R61")
      (value "10k")
      (footprint "eagle-import:0805")
      (libsource (lib "eagle-import") (part "0.3OHM-0805-1/8W-1%"))
    )
    (comp (ref "R62")
      (value "330")
      (footprint "eagle-import:0805")
      (libsource (lib "eagle-import") (part "0.3OHM-0805-1/8W-1%"))
    )
    (comp (ref "R63")
      (value "10k")
      (footprint "eagle-import:0805")
      (libsource (lib "eagle-import") (part "0.3OHM-0805-1/8W-1%"))
    )
    (comp (ref "R64")
      (value "330")
      (footprint "eagle-import:0805")
      (libsource (lib "eagle-import") (part "0.3OHM-0805-1/8W-1%"))
    )
    (comp (ref "R65")
      (value "10k")
      (footprint "eagle-import:0805")
      (libsource (lib "eagle-import") (part "0.3OHM-0805-1/8W-1%"))
    )
    (comp (ref "R66")
      (value "330")
      (footprint "eagle-import:0805")
      (libsource (lib "eagle-import") (part "0.3OHM-0805-1/8W-1%"))
    )
    (comp (ref "R67")
      (value "10k")
      (footprint "eagle-import:0805")
      (libsource (lib "eagle-import") (part "0.3OHM-0805-1/8W-1%"))
    )
    (comp (ref "R68")
      (value "330")
      (footprint "eagle-import:0805")
      (libsource (lib "eagle-import") (part "0.3OHM-0805-1/8W-1%"))
    )
    (comp (ref "R69")
      (value "10k")
      (footprint "eagle-import:0805")
      (libsource (lib "eagle-import") (part "0.3OHM-0805-1/8W-1%"))
    )
    (comp (ref "RESET")
      (value "PINHD-2X4")
      (footprint "eagle-import:2X04")
      (libsource (lib "eagle-import") (part "PINHD-2X4"))
    )
    (comp (ref "S1")
      (value "219-8LPST")
      (footprint "eagle-import:2198LPST")
      (fields (field (name "MOUSER_PART_NUMBER") "774-2198LPST"))
      (libsource (lib "eagle-import") (part "219-8LPST"))
    )
    (comp (ref "S2")
      (value "219-8LPST")
      (footprint "eagle-import:2198LPST")
      (fields (field (name "MOUSER_PART_NUMBER") "774-2198LPST"))
      (libsource (lib "eagle-import") (part "219-8LPST"))
    )
    (comp (ref "S17")
      (value "SS12SDP2")
      (footprint "eagle-import:SS12SDP2")
      (fields (field (name "MOUSER_PART_NUMBER") "633-SS12SDP2"))
      (libsource (lib "eagle-import") (part "SS12SDP2"))
    )
    (comp (ref "S18")
      (value "SS12SDP2")
      (footprint "eagle-import:SS12SDP2")
      (fields (field (name "MOUSER_PART_NUMBER") "633-SS12SDP2"))
      (libsource (lib "eagle-import") (part "SS12SDP2"))
    )
    (comp (ref "SDCARD")
      (value "PINHD-2X4")
      (footprint "eagle-import:2X04")
      (libsource (lib "eagle-import") (part "PINHD-2X4"))
    )
    (comp (ref "SDCARD_CONNECTOR")
      (value "PINHD-2X6")
      (footprint "eagle-import:2X06")
      (libsource (lib "eagle-import") (part "PINHD-2X6"))
    )
    (comp (ref "SYS_CLK")
      (value "2985-6004")
      (footprint "eagle-import:29856004")
      (fields (field (name "MOUSER_PART_NUMBER") "523-2985-6004"))
      (libsource (lib "eagle-import") (part "2985-6004"))
    )
    (comp (ref "U$1")
      (value "2X41_HEADER")
      (footprint "eagle-import:2X41_HEADER")
      (libsource (lib "eagle-import") (part "2X41_HEADER"))
    )
    (comp (ref "U$2")
      (value "2X41_HEADER")
      (footprint "eagle-import:2X41_HEADER")
      (libsource (lib "eagle-import") (part "2X41_HEADER"))
    )
    (comp (ref "U$3")
      (value "2X41_HEADER")
      (footprint "eagle-import:2X41_HEADER")
      (libsource (lib "eagle-import") (part "2X41_HEADER"))
    )
    (comp (ref "U$4")
      (value "2X41_HEADER")
      (footprint "eagle-import:2X41_HEADER")
      (libsource (lib "eagle-import") (part "2X41_HEADER"))
    )
    (comp (ref "UART")
      (value "PINHD-2X2")
      (footprint "eagle-import:2X02")
      (libsource (lib "eagle-import") (part "PINHD-2X2"))
    )
    (comp (ref "USB-UART_1")
      (value "PINHD-1X4")
      (footprint "eagle-import:1X04")
      (libsource (lib "eagle-import") (part "PINHD-1X4"))
    )
    (comp (ref "USB-UART_2")
      (value "PINHD-1X4")
      (footprint "eagle-import:1X04")
      (libsource (lib "eagle-import") (part "PINHD-1X4"))
    )
    (comp (ref "VDD")
      (value "PINHD-2X2")
      (footprint "eagle-import:2X02")
      (libsource (lib "eagle-import") (part "pinhead_325_PINHD-2X2"))
    )
    (comp (ref "VDDO")
      (value "PINHD-2X2")
      (footprint "eagle-import:2X02")
      (libsource (lib "eagle-import") (part "pinhead_325_PINHD-2X2"))
    )
    (comp (ref "VDD_3V3")
      (value "PINHD-2X2")
      (footprint "eagle-import:2X02")
      (libsource (lib "eagle-import") (part "pinhead_325_PINHD-2X2"))
    )
  )
  (nets
    (net (code "1") (name "17") (class "Default")
      (node (ref "U$1") (pin "17") (pinfunction "17_17") (pintype "bidirectional"))
    )
    (net (code "2") (name "18") (class "Default")
      (node (ref "U$1") (pin "20") (pinfunction "20_20") (pintype "bidirectional"))
    )
    (net (code "3") (name "19") (class "Default")
      (node (ref "U$1") (pin "19") (pinfunction "19_19") (pintype "bidirectional"))
    )
    (net (code "4") (name "20") (class "Default")
      (node (ref "U$1") (pin "22") (pinfunction "22_22") (pintype "bidirectional"))
    )
    (net (code "5") (name "21") (class "Default")
      (node (ref "U$1") (pin "21") (pinfunction "21_21") (pintype "bidirectional"))
    )
    (net (code "6") (name "22") (class "Default")
      (node (ref "U$1") (pin "24") (pinfunction "24_24") (pintype "bidirectional"))
    )
    (net (code "7") (name "23") (class "Default")
      (node (ref "U$1") (pin "23") (pinfunction "23_23") (pintype "bidirectional"))
    )
    (net (code "8") (name "24") (class "Default")
      (node (ref "U$1") (pin "26") (pinfunction "26_26") (pintype "bidirectional"))
    )
    (net (code "9") (name "57") (class "Default")
      (node (ref "U$2") (pin "17") (pinfunction "17_17") (pintype "bidirectional"))
    )
    (net (code "10") (name "58") (class "Default")
      (node (ref "U$2") (pin "20") (pinfunction "20_20") (pintype "bidirectional"))
    )
    (net (code "11") (name "59") (class "Default")
      (node (ref "U$2") (pin "19") (pinfunction "19_19") (pintype "bidirectional"))
    )
    (net (code "12") (name "60") (class "Default")
      (node (ref "U$2") (pin "22") (pinfunction "22_22") (pintype "bidirectional"))
    )
    (net (code "13") (name "61") (class "Default")
      (node (ref "U$2") (pin "21") (pinfunction "21_21") (pintype "bidirectional"))
    )
    (net (code "14") (name "62") (class "Default")
      (node (ref "U$2") (pin "24") (pinfunction "24_24") (pintype "bidirectional"))
    )
    (net (code "15") (name "63") (class "Default")
      (node (ref "U$2") (pin "23") (pinfunction "23_23") (pintype "bidirectional"))
    )
    (net (code "16") (name "64") (class "Default")
      (node (ref "U$2") (pin "26") (pinfunction "26_26") (pintype "bidirectional"))
    )
    (net (code "17") (name "97") (class "Default")
      (node (ref "U$3") (pin "17") (pinfunction "17_17") (pintype "bidirectional"))
    )
    (net (code "18") (name "98") (class "Default")
      (node (ref "U$3") (pin "20") (pinfunction "20_20") (pintype "bidirectional"))
    )
    (net (code "19") (name "99") (class "Default")
      (node (ref "U$3") (pin "19") (pinfunction "19_19") (pintype "bidirectional"))
    )
    (net (code "20") (name "100") (class "Default")
      (node (ref "U$3") (pin "22") (pinfunction "22_22") (pintype "bidirectional"))
    )
    (net (code "21") (name "101") (class "Default")
      (node (ref "U$3") (pin "21") (pinfunction "21_21") (pintype "bidirectional"))
    )
    (net (code "22") (name "102") (class "Default")
      (node (ref "U$3") (pin "24") (pinfunction "24_24") (pintype "bidirectional"))
    )
    (net (code "23") (name "103") (class "Default")
      (node (ref "U$3") (pin "23") (pinfunction "23_23") (pintype "bidirectional"))
    )
    (net (code "24") (name "104") (class "Default")
      (node (ref "U$3") (pin "26") (pinfunction "26_26") (pintype "bidirectional"))
    )
    (net (code "25") (name "120") (class "Default")
      (node (ref "U$3") (pin "42") (pinfunction "42_42") (pintype "bidirectional"))
    )
    (net (code "26") (name "137") (class "Default")
      (node (ref "U$4") (pin "17") (pinfunction "17_17") (pintype "bidirectional"))
    )
    (net (code "27") (name "138") (class "Default")
      (node (ref "U$4") (pin "20") (pinfunction "20_20") (pintype "bidirectional"))
    )
    (net (code "28") (name "139") (class "Default")
      (node (ref "U$4") (pin "19") (pinfunction "19_19") (pintype "bidirectional"))
    )
    (net (code "29") (name "140") (class "Default")
      (node (ref "U$4") (pin "22") (pinfunction "22_22") (pintype "bidirectional"))
    )
    (net (code "30") (name "141") (class "Default")
      (node (ref "U$4") (pin "21") (pinfunction "21_21") (pintype "bidirectional"))
    )
    (net (code "31") (name "142") (class "Default")
      (node (ref "U$4") (pin "24") (pinfunction "24_24") (pintype "bidirectional"))
    )
    (net (code "32") (name "143") (class "Default")
      (node (ref "U$4") (pin "23") (pinfunction "23_23") (pintype "bidirectional"))
    )
    (net (code "33") (name "144") (class "Default")
      (node (ref "U$4") (pin "26") (pinfunction "26_26") (pintype "bidirectional"))
    )
    (net (code "34") (name "FPGA2_I_CLOCKCTRL_0_CLK0") (class "Default")
      (node (ref "CLOCKCTRL_0") (pin "5") (pinfunction "5_5") (pintype "bidirectional"))
      (node (ref "U$3") (pin "10") (pinfunction "10_10") (pintype "bidirectional"))
    )
    (net (code "35") (name "FPGA2_I_CLOCKCTRL_1_CLK0") (class "Default")
      (node (ref "CLOCKCTRL_1") (pin "5") (pinfunction "5_5") (pintype "bidirectional"))
      (node (ref "U$3") (pin "7") (pinfunction "7_7") (pintype "bidirectional"))
    )
    (net (code "36") (name "FPGA2_I_CLOCKCTRL_2_CLK0") (class "Default")
      (node (ref "CLOCKCTRL_2") (pin "5") (pinfunction "5_5") (pintype "bidirectional"))
      (node (ref "U$3") (pin "8") (pinfunction "8_8") (pintype "bidirectional"))
    )
    (net (code "37") (name "FPGA2_I_EXTSER_IN_BITS[0]") (class "Default")
      (node (ref "GPIO_0") (pin "21") (pinfunction "21_21") (pintype "passive"))
      (node (ref "U$2") (pin "31") (pinfunction "31_31") (pintype "bidirectional"))
    )
    (net (code "38") (name "FPGA2_I_EXTSER_IN_BITS[1]") (class "Default")
      (node (ref "GPIO_0") (pin "19") (pinfunction "19_19") (pintype "passive"))
      (node (ref "U$2") (pin "34") (pinfunction "34_34") (pintype "bidirectional"))
    )
    (net (code "39") (name "FPGA2_I_EXTSER_IN_BITS[2]") (class "Default")
      (node (ref "GPIO_0") (pin "17") (pinfunction "17_17") (pintype "passive"))
      (node (ref "U$2") (pin "33") (pinfunction "33_33") (pintype "bidirectional"))
    )
    (net (code "40") (name "FPGA2_I_EXTSER_IN_BITS[3]") (class "Default")
      (node (ref "GPIO_0") (pin "15") (pinfunction "15_15") (pintype "passive"))
      (node (ref "U$2") (pin "36") (pinfunction "36_36") (pintype "bidirectional"))
    )
    (net (code "41") (name "FPGA2_I_EXTSER_IN_BITS[4]") (class "Default")
      (node (ref "GPIO_0") (pin "13") (pinfunction "13_13") (pintype "passive"))
      (node (ref "U$2") (pin "35") (pinfunction "35_35") (pintype "bidirectional"))
    )
    (net (code "42") (name "FPGA2_I_EXTSER_IN_BITS[5]") (class "Default")
      (node (ref "GPIO_0") (pin "9") (pinfunction "9_9") (pintype "passive"))
      (node (ref "U$2") (pin "38") (pinfunction "38_38") (pintype "bidirectional"))
    )
    (net (code "43") (name "FPGA2_I_EXTSER_IN_BITS[6]") (class "Default")
      (node (ref "GPIO_0") (pin "7") (pinfunction "7_7") (pintype "passive"))
      (node (ref "U$2") (pin "40") (pinfunction "40_40") (pintype "bidirectional"))
    )
    (net (code "44") (name "FPGA2_I_EXTSER_IN_BITS[7]") (class "Default")
      (node (ref "GPIO_0") (pin "5") (pinfunction "5_5") (pintype "passive"))
      (node (ref "U$2") (pin "42") (pinfunction "42_42") (pintype "bidirectional"))
    )
    (net (code "45") (name "FPGA2_I_EXTSER_IN_VALID") (class "Default")
      (node (ref "GPIO_0") (pin "23") (pinfunction "23_23") (pintype "passive"))
      (node (ref "U$2") (pin "32") (pinfunction "32_32") (pintype "bidirectional"))
    )
    (net (code "46") (name "FPGA2_I_EXTSER_OUT_READY") (class "Default")
      (node (ref "GPIO_0") (pin "25") (pinfunction "25_25") (pintype "passive"))
      (node (ref "U$2") (pin "29") (pinfunction "29_29") (pintype "bidirectional"))
    )
    (net (code "47") (name "FPGA2_I_JRST_N") (class "Default")
      (node (ref "RESET") (pin "1") (pinfunction "1_1") (pintype "passive"))
      (node (ref "RESET") (pin "3") (pinfunction "3_3") (pintype "passive"))
      (node (ref "U$3") (pin "6") (pinfunction "6_6") (pintype "bidirectional"))
    )
    (net (code "48") (name "FPGA2_I_MEMSER_IN_BITS[0]") (class "Default")
      (node (ref "GPIO_1") (pin "7") (pinfunction "7_7") (pintype "passive"))
      (node (ref "U$1") (pin "28") (pinfunction "28_28") (pintype "bidirectional"))
    )
    (net (code "49") (name "FPGA2_I_MEMSER_IN_BITS[1]") (class "Default")
      (node (ref "GPIO_1") (pin "5") (pinfunction "5_5") (pintype "passive"))
      (node (ref "U$1") (pin "30") (pinfunction "30_30") (pintype "bidirectional"))
    )
    (net (code "50") (name "FPGA2_I_MEMSER_IN_BITS[2]") (class "Default")
      (node (ref "GPIO_1") (pin "1") (pinfunction "1_1") (pintype "passive"))
      (node (ref "U$1") (pin "29") (pinfunction "29_29") (pintype "bidirectional"))
    )
    (net (code "51") (name "FPGA2_I_MEMSER_IN_BITS[3]") (class "Default")
      (node (ref "GPIO_0") (pin "39") (pinfunction "39_39") (pintype "passive"))
      (node (ref "U$1") (pin "32") (pinfunction "32_32") (pintype "bidirectional"))
    )
    (net (code "52") (name "FPGA2_I_MEMSER_IN_BITS[4]") (class "Default")
      (node (ref "GPIO_0") (pin "37") (pinfunction "37_37") (pintype "passive"))
      (node (ref "U$1") (pin "31") (pinfunction "31_31") (pintype "bidirectional"))
    )
    (net (code "53") (name "FPGA2_I_MEMSER_IN_BITS[5]") (class "Default")
      (node (ref "GPIO_0") (pin "35") (pinfunction "35_35") (pintype "passive"))
      (node (ref "U$1") (pin "34") (pinfunction "34_34") (pintype "bidirectional"))
    )
    (net (code "54") (name "FPGA2_I_MEMSER_IN_BITS[6]") (class "Default")
      (node (ref "GPIO_0") (pin "33") (pinfunction "33_33") (pintype "passive"))
      (node (ref "U$1") (pin "33") (pinfunction "33_33") (pintype "bidirectional"))
    )
    (net (code "55") (name "FPGA2_I_MEMSER_IN_BITS[7]") (class "Default")
      (node (ref "GPIO_0") (pin "31") (pinfunction "31_31") (pintype "passive"))
      (node (ref "U$1") (pin "36") (pinfunction "36_36") (pintype "bidirectional"))
    )
    (net (code "56") (name "FPGA2_I_MEMSER_IN_VALID") (class "Default")
      (node (ref "GPIO_1") (pin "9") (pinfunction "9_9") (pintype "passive"))
      (node (ref "U$1") (pin "18") (pinfunction "18_18") (pintype "bidirectional"))
    )
    (net (code "57") (name "FPGA2_I_MEMSER_OUT_READY") (class "Default")
      (node (ref "GPIO_1") (pin "13") (pinfunction "13_13") (pintype "passive"))
      (node (ref "U$1") (pin "16") (pinfunction "16_16") (pintype "bidirectional"))
    )
    (net (code "58") (name "FPGA2_I_PLL_CLK_OUT2") (class "Default")
      (node (ref "PLL_CLK_OUT2") (pin "5") (pinfunction "5_5") (pintype "bidirectional"))
      (node (ref "U$3") (pin "5") (pinfunction "5_5") (pintype "bidirectional"))
    )
    (net (code "59") (name "FPGA2_I_RST_N") (class "Default")
      (node (ref "RESET") (pin "5") (pinfunction "5_5") (pintype "passive"))
      (node (ref "RESET") (pin "7") (pinfunction "7_7") (pintype "passive"))
      (node (ref "U$3") (pin "4") (pinfunction "4_4") (pintype "bidirectional"))
    )
    (net (code "60") (name "FPGA2_I_SYS_CLK") (class "Default")
      (node (ref "SYS_CLK") (pin "5") (pinfunction "5_5") (pintype "bidirectional"))
      (node (ref "U$3") (pin "9") (pinfunction "9_9") (pintype "bidirectional"))
    )
    (net (code "61") (name "FPGA2_O_EXTSER_IN_READY") (class "Default")
      (node (ref "GPIO_1") (pin "17") (pinfunction "17_17") (pintype "passive"))
      (node (ref "U$2") (pin "7") (pinfunction "7_7") (pintype "bidirectional"))
    )
    (net (code "62") (name "FPGA2_O_EXTSER_OUT_BITS[0]") (class "Default")
      (node (ref "GPIO_1") (pin "37") (pinfunction "37_37") (pintype "passive"))
      (node (ref "U$2") (pin "9") (pinfunction "9_9") (pintype "bidirectional"))
    )
    (net (code "63") (name "FPGA2_O_EXTSER_OUT_BITS[1]") (class "Default")
      (node (ref "GPIO_1") (pin "35") (pinfunction "35_35") (pintype "passive"))
      (node (ref "U$2") (pin "12") (pinfunction "12_12") (pintype "bidirectional"))
    )
    (net (code "64") (name "FPGA2_O_EXTSER_OUT_BITS[2]") (class "Default")
      (node (ref "GPIO_1") (pin "33") (pinfunction "33_33") (pintype "passive"))
      (node (ref "U$2") (pin "11") (pinfunction "11_11") (pintype "bidirectional"))
    )
    (net (code "65") (name "FPGA2_O_EXTSER_OUT_BITS[3]") (class "Default")
      (node (ref "GPIO_1") (pin "31") (pinfunction "31_31") (pintype "passive"))
      (node (ref "U$2") (pin "14") (pinfunction "14_14") (pintype "bidirectional"))
    )
    (net (code "66") (name "FPGA2_O_EXTSER_OUT_BITS[4]") (class "Default")
      (node (ref "GPIO_1") (pin "27") (pinfunction "27_27") (pintype "passive"))
      (node (ref "U$2") (pin "16") (pinfunction "16_16") (pintype "bidirectional"))
    )
    (net (code "67") (name "FPGA2_O_EXTSER_OUT_BITS[5]") (class "Default")
      (node (ref "GPIO_1") (pin "25") (pinfunction "25_25") (pintype "passive"))
      (node (ref "U$2") (pin "18") (pinfunction "18_18") (pintype "bidirectional"))
    )
    (net (code "68") (name "FPGA2_O_EXTSER_OUT_BITS[6]") (class "Default")
      (node (ref "GPIO_1") (pin "21") (pinfunction "21_21") (pintype "passive"))
      (node (ref "U$2") (pin "28") (pinfunction "28_28") (pintype "bidirectional"))
    )
    (net (code "69") (name "FPGA2_O_EXTSER_OUT_BITS[7]") (class "Default")
      (node (ref "GPIO_1") (pin "19") (pinfunction "19_19") (pintype "passive"))
      (node (ref "U$2") (pin "30") (pinfunction "30_30") (pintype "bidirectional"))
    )
    (net (code "70") (name "FPGA2_O_EXTSER_OUT_VALID") (class "Default")
      (node (ref "GPIO_1") (pin "39") (pinfunction "39_39") (pintype "passive"))
      (node (ref "U$2") (pin "10") (pinfunction "10_10") (pintype "bidirectional"))
    )
    (net (code "71") (name "FPGA2_O_MEMSER_IN_READY") (class "Default")
      (node (ref "GPIO_2") (pin "5") (pinfunction "5_5") (pintype "passive"))
      (node (ref "U$1") (pin "4") (pinfunction "4_4") (pintype "bidirectional"))
    )
    (net (code "72") (name "FPGA2_O_MEMSER_OUT_BITS[0]") (class "Default")
      (node (ref "GPIO_2") (pin "23") (pinfunction "23_23") (pintype "passive"))
      (node (ref "U$1") (pin "5") (pinfunction "5_5") (pintype "bidirectional"))
    )
    (net (code "73") (name "FPGA2_O_MEMSER_OUT_BITS[1]") (class "Default")
      (node (ref "GPIO_2") (pin "21") (pinfunction "21_21") (pintype "passive"))
      (node (ref "U$1") (pin "8") (pinfunction "8_8") (pintype "bidirectional"))
    )
    (net (code "74") (name "FPGA2_O_MEMSER_OUT_BITS[2]") (class "Default")
      (node (ref "GPIO_2") (pin "19") (pinfunction "19_19") (pintype "passive"))
      (node (ref "U$1") (pin "7") (pinfunction "7_7") (pintype "bidirectional"))
    )
    (net (code "75") (name "FPGA2_O_MEMSER_OUT_BITS[3]") (class "Default")
      (node (ref "GPIO_2") (pin "17") (pinfunction "17_17") (pintype "passive"))
      (node (ref "U$1") (pin "10") (pinfunction "10_10") (pintype "bidirectional"))
    )
    (net (code "76") (name "FPGA2_O_MEMSER_OUT_BITS[4]") (class "Default")
      (node (ref "GPIO_2") (pin "15") (pinfunction "15_15") (pintype "passive"))
      (node (ref "U$1") (pin "9") (pinfunction "9_9") (pintype "bidirectional"))
    )
    (net (code "77") (name "FPGA2_O_MEMSER_OUT_BITS[5]") (class "Default")
      (node (ref "GPIO_2") (pin "13") (pinfunction "13_13") (pintype "passive"))
      (node (ref "U$1") (pin "12") (pinfunction "12_12") (pintype "bidirectional"))
    )
    (net (code "78") (name "FPGA2_O_MEMSER_OUT_BITS[6]") (class "Default")
      (node (ref "GPIO_2") (pin "9") (pinfunction "9_9") (pintype "passive"))
      (node (ref "U$1") (pin "11") (pinfunction "11_11") (pintype "bidirectional"))
    )
    (net (code "79") (name "FPGA2_O_MEMSER_OUT_BITS[7]") (class "Default")
      (node (ref "GPIO_2") (pin "7") (pinfunction "7_7") (pintype "passive"))
      (node (ref "U$1") (pin "14") (pinfunction "14_14") (pintype "bidirectional"))
    )
    (net (code "80") (name "FPGA2_O_MEMSER_OUT_VALID") (class "Default")
      (node (ref "GPIO_2") (pin "25") (pinfunction "25_25") (pintype "passive"))
      (node (ref "U$1") (pin "6") (pinfunction "6_6") (pintype "bidirectional"))
    )
    (net (code "81") (name "GND") (class "Default")
      (node (ref "C1") (pin "2") (pinfunction "2_2") (pintype "passive"))
      (node (ref "C11") (pin "2") (pinfunction "2_2") (pintype "passive"))
      (node (ref "C13") (pin "2") (pinfunction "2_2") (pintype "passive"))
      (node (ref "C14") (pin "2") (pinfunction "2_2") (pintype "passive"))
      (node (ref "C15") (pin "2") (pinfunction "2_2") (pintype "passive"))
      (node (ref "C16") (pin "2") (pinfunction "2_2") (pintype "passive"))
      (node (ref "C17") (pin "2") (pinfunction "2_2") (pintype "passive"))
      (node (ref "C18") (pin "2") (pinfunction "2_2") (pintype "passive"))
      (node (ref "C19") (pin "2") (pinfunction "2_2") (pintype "passive"))
      (node (ref "C2") (pin "2") (pinfunction "2_2") (pintype "passive"))
      (node (ref "C20") (pin "2") (pinfunction "2_2") (pintype "passive"))
      (node (ref "C21") (pin "2") (pinfunction "2_2") (pintype "passive"))
      (node (ref "C22") (pin "2") (pinfunction "2_2") (pintype "passive"))
      (node (ref "C23") (pin "2") (pinfunction "2_2") (pintype "passive"))
      (node (ref "C24") (pin "2") (pinfunction "2_2") (pintype "passive"))
      (node (ref "C26") (pin "2") (pinfunction "2_2") (pintype "passive"))
      (node (ref "C27") (pin "2") (pinfunction "2_2") (pintype "passive"))
      (node (ref "C28") (pin "2") (pinfunction "2_2") (pintype "passive"))
      (node (ref "C29") (pin "2") (pinfunction "2_2") (pintype "passive"))
      (node (ref "C3") (pin "2") (pinfunction "2_2") (pintype "passive"))
      (node (ref "C30") (pin "2") (pinfunction "2_2") (pintype "passive"))
      (node (ref "C4") (pin "2") (pinfunction "2_2") (pintype "passive"))
      (node (ref "C5") (pin "2") (pinfunction "2_2") (pintype "passive"))
      (node (ref "C6") (pin "2") (pinfunction "2_2") (pintype "passive"))
      (node (ref "C7") (pin "2") (pinfunction "2_2") (pintype "passive"))
      (node (ref "C8") (pin "2") (pinfunction "2_2") (pintype "passive"))
      (node (ref "C9") (pin "2") (pinfunction "2_2") (pintype "passive"))
      (node (ref "CLOCKCTRL_0") (pin "1") (pinfunction "1_1") (pintype "bidirectional"))
      (node (ref "CLOCKCTRL_0") (pin "2") (pinfunction "2_2") (pintype "bidirectional"))
      (node (ref "CLOCKCTRL_0") (pin "3") (pinfunction "3_3") (pintype "bidirectional"))
      (node (ref "CLOCKCTRL_0") (pin "4") (pinfunction "4_4") (pintype "bidirectional"))
      (node (ref "CLOCKCTRL_1") (pin "1") (pinfunction "1_1") (pintype "bidirectional"))
      (node (ref "CLOCKCTRL_1") (pin "2") (pinfunction "2_2") (pintype "bidirectional"))
      (node (ref "CLOCKCTRL_1") (pin "3") (pinfunction "3_3") (pintype "bidirectional"))
      (node (ref "CLOCKCTRL_1") (pin "4") (pinfunction "4_4") (pintype "bidirectional"))
      (node (ref "CLOCKCTRL_2") (pin "1") (pinfunction "1_1") (pintype "bidirectional"))
      (node (ref "CLOCKCTRL_2") (pin "2") (pinfunction "2_2") (pintype "bidirectional"))
      (node (ref "CLOCKCTRL_2") (pin "3") (pinfunction "3_3") (pintype "bidirectional"))
      (node (ref "CLOCKCTRL_2") (pin "4") (pinfunction "4_4") (pintype "bidirectional"))
      (node (ref "FLASH_CONNECTOR") (pin "3") (pinfunction "3_3") (pintype "passive"))
      (node (ref "FLASH_CONNECTOR") (pin "4") (pinfunction "4_4") (pintype "passive"))
      (node (ref "GPIO_0") (pin "12") (pinfunction "12_12") (pintype "passive"))
      (node (ref "GPIO_0") (pin "30") (pinfunction "30_30") (pintype "passive"))
      (node (ref "GPIO_1") (pin "12") (pinfunction "12_12") (pintype "passive"))
      (node (ref "GPIO_1") (pin "30") (pinfunction "30_30") (pintype "passive"))
      (node (ref "GPIO_2") (pin "12") (pinfunction "12_12") (pintype "passive"))
      (node (ref "GPIO_2") (pin "30") (pinfunction "30_30") (pintype "passive"))
      (node (ref "GPIO_3") (pin "12") (pinfunction "12_12") (pintype "passive"))
      (node (ref "GPIO_3") (pin "30") (pinfunction "30_30") (pintype "passive"))
      (node (ref "IC1") (pin "11") (pinfunction "GND_11") (pintype "bidirectional"))
      (node (ref "IC2") (pin "11") (pinfunction "GND_11") (pintype "bidirectional"))
      (node (ref "IC3") (pin "2") (pinfunction "GND_2") (pintype "power_in"))
      (node (ref "IC3") (pin "3") (pinfunction "~{EN}_3") (pintype "bidirectional"))
      (node (ref "IC4") (pin "11") (pinfunction "GND_11") (pintype "bidirectional"))
      (node (ref "IC5") (pin "2") (pinfunction "GND_2") (pintype "power_in"))
      (node (ref "IC5") (pin "3") (pinfunction "~{EN}_3") (pintype "bidirectional"))
      (node (ref "IC6") (pin "11") (pinfunction "GND_11") (pintype "bidirectional"))
      (node (ref "IC7") (pin "2") (pinfunction "GND_2") (pintype "power_in"))
      (node (ref "IC7") (pin "3") (pinfunction "~{EN}_3") (pintype "bidirectional"))
      (node (ref "JTAG_CONNECTOR") (pin "10") (pinfunction "10_10") (pintype "passive"))
      (node (ref "JTAG_CONNECTOR") (pin "12") (pinfunction "12_12") (pintype "passive"))
      (node (ref "JTAG_CONNECTOR") (pin "14") (pinfunction "14_14") (pintype "passive"))
      (node (ref "JTAG_CONNECTOR") (pin "16") (pinfunction "16_16") (pintype "passive"))
      (node (ref "JTAG_CONNECTOR") (pin "18") (pinfunction "18_18") (pintype "passive"))
      (node (ref "JTAG_CONNECTOR") (pin "20") (pinfunction "20_20") (pintype "passive"))
      (node (ref "JTAG_CONNECTOR") (pin "4") (pinfunction "4_4") (pintype "passive"))
      (node (ref "JTAG_CONNECTOR") (pin "6") (pinfunction "6_6") (pintype "passive"))
      (node (ref "JTAG_CONNECTOR") (pin "8") (pinfunction "8_8") (pintype "passive"))
      (node (ref "PLL_CLK_OUT2") (pin "1") (pinfunction "1_1") (pintype "bidirectional"))
      (node (ref "PLL_CLK_OUT2") (pin "2") (pinfunction "2_2") (pintype "bidirectional"))
      (node (ref "PLL_CLK_OUT2") (pin "3") (pinfunction "3_3") (pintype "bidirectional"))
      (node (ref "PLL_CLK_OUT2") (pin "4") (pinfunction "4_4") (pintype "bidirectional"))
      (node (ref "Q1") (pin "2") (pinfunction "S_2") (pintype "bidirectional"))
      (node (ref "Q10") (pin "2") (pinfunction "S_2") (pintype "bidirectional"))
      (node (ref "Q11") (pin "2") (pinfunction "S_2") (pintype "bidirectional"))
      (node (ref "Q12") (pin "2") (pinfunction "S_2") (pintype "bidirectional"))
      (node (ref "Q13") (pin "2") (pinfunction "S_2") (pintype "bidirectional"))
      (node (ref "Q14") (pin "2") (pinfunction "S_2") (pintype "bidirectional"))
      (node (ref "Q15") (pin "2") (pinfunction "S_2") (pintype "bidirectional"))
      (node (ref "Q16") (pin "2") (pinfunction "S_2") (pintype "bidirectional"))
      (node (ref "Q17") (pin "2") (pinfunction "S_2") (pintype "bidirectional"))
      (node (ref "Q18") (pin "2") (pinfunction "S_2") (pintype "bidirectional"))
      (node (ref "Q19") (pin "2") (pinfunction "S_2") (pintype "bidirectional"))
      (node (ref "Q2") (pin "2") (pinfunction "S_2") (pintype "bidirectional"))
      (node (ref "Q20") (pin "2") (pinfunction "S_2") (pintype "bidirectional"))
      (node (ref "Q21") (pin "2") (pinfunction "S_2") (pintype "bidirectional"))
      (node (ref "Q3") (pin "2") (pinfunction "S_2") (pintype "bidirectional"))
      (node (ref "Q4") (pin "2") (pinfunction "S_2") (pintype "bidirectional"))
      (node (ref "Q5") (pin "2") (pinfunction "S_2") (pintype "bidirectional"))
      (node (ref "Q6") (pin "2") (pinfunction "S_2") (pintype "bidirectional"))
      (node (ref "Q7") (pin "2") (pinfunction "S_2") (pintype "bidirectional"))
      (node (ref "Q8") (pin "2") (pinfunction "S_2") (pintype "bidirectional"))
      (node (ref "Q9") (pin "2") (pinfunction "S_2") (pintype "bidirectional"))
      (node (ref "R10") (pin "2") (pinfunction "2_2") (pintype "passive"))
      (node (ref "R12") (pin "2") (pinfunction "2_2") (pintype "passive"))
      (node (ref "R14") (pin "2") (pinfunction "2_2") (pintype "passive"))
      (node (ref "R16") (pin "2") (pinfunction "2_2") (pintype "passive"))
      (node (ref "R18") (pin "2") (pinfunction "2_2") (pintype "passive"))
      (node (ref "R2") (pin "2") (pinfunction "2_2") (pintype "passive"))
      (node (ref "R20") (pin "2") (pinfunction "2_2") (pintype "passive"))
      (node (ref "R22") (pin "2") (pinfunction "2_2") (pintype "passive"))
      (node (ref "R24") (pin "2") (pinfunction "2_2") (pintype "passive"))
      (node (ref "R38") (pin "2") (pinfunction "2_2") (pintype "passive"))
      (node (ref "R4") (pin "2") (pinfunction "2_2") (pintype "passive"))
      (node (ref "R40") (pin "2") (pinfunction "2_2") (pintype "passive"))
      (node (ref "R43") (pin "2") (pinfunction "2_2") (pintype "passive"))
      (node (ref "R45") (pin "2") (pinfunction "2_2") (pintype "passive"))
      (node (ref "R46") (pin "2") (pinfunction "2_2") (pintype "passive"))
      (node (ref "R48") (pin "2") (pinfunction "2_2") (pintype "passive"))
      (node (ref "R50") (pin "2") (pinfunction "2_2") (pintype "passive"))
      (node (ref "R52") (pin "2") (pinfunction "2_2") (pintype "passive"))
      (node (ref "R57") (pin "2") (pinfunction "2_2") (pintype "passive"))
      (node (ref "R59") (pin "2") (pinfunction "2_2") (pintype "passive"))
      (node (ref "R6") (pin "2") (pinfunction "2_2") (pintype "passive"))
      (node (ref "R61") (pin "2") (pinfunction "2_2") (pintype "passive"))
      (node (ref "R63") (pin "2") (pinfunction "2_2") (pintype "passive"))
      (node (ref "R65") (pin "2") (pinfunction "2_2") (pintype "passive"))
      (node (ref "R67") (pin "2") (pinfunction "2_2") (pintype "passive"))
      (node (ref "R69") (pin "2") (pinfunction "2_2") (pintype "passive"))
      (node (ref "R8") (pin "2") (pinfunction "2_2") (pintype "passive"))
      (node (ref "S1") (pin "10") (pinfunction "10_10") (pintype "bidirectional"))
      (node (ref "S1") (pin "11") (pinfunction "11_11") (pintype "bidirectional"))
      (node (ref "S1") (pin "12") (pinfunction "12_12") (pintype "bidirectional"))
      (node (ref "S1") (pin "13") (pinfunction "13_13") (pintype "bidirectional"))
      (node (ref "S1") (pin "14") (pinfunction "14_14") (pintype "bidirectional"))
      (node (ref "S1") (pin "15") (pinfunction "15_15") (pintype "bidirectional"))
      (node (ref "S1") (pin "16") (pinfunction "16_16") (pintype "bidirectional"))
      (node (ref "S1") (pin "9") (pinfunction "9_9") (pintype "bidirectional"))
      (node (ref "S17") (pin "3") (pinfunction "ON_2_3") (pintype "bidirectional"))
      (node (ref "S18") (pin "3") (pinfunction "ON_2_3") (pintype "bidirectional"))
      (node (ref "S2") (pin "10") (pinfunction "10_10") (pintype "bidirectional"))
      (node (ref "S2") (pin "11") (pinfunction "11_11") (pintype "bidirectional"))
      (node (ref "S2") (pin "12") (pinfunction "12_12") (pintype "bidirectional"))
      (node (ref "S2") (pin "13") (pinfunction "13_13") (pintype "bidirectional"))
      (node (ref "S2") (pin "14") (pinfunction "14_14") (pintype "bidirectional"))
      (node (ref "S2") (pin "15") (pinfunction "15_15") (pintype "bidirectional"))
      (node (ref "S2") (pin "16") (pinfunction "16_16") (pintype "bidirectional"))
      (node (ref "S2") (pin "9") (pinfunction "9_9") (pintype "bidirectional"))
      (node (ref "SDCARD_CONNECTOR") (pin "3") (pinfunction "3_3") (pintype "passive"))
      (node (ref "SDCARD_CONNECTOR") (pin "4") (pinfunction "4_4") (pintype "passive"))
      (node (ref "SYS_CLK") (pin "1") (pinfunction "1_1") (pintype "bidirectional"))
      (node (ref "SYS_CLK") (pin "2") (pinfunction "2_2") (pintype "bidirectional"))
      (node (ref "SYS_CLK") (pin "3") (pinfunction "3_3") (pintype "bidirectional"))
      (node (ref "SYS_CLK") (pin "4") (pinfunction "4_4") (pintype "bidirectional"))
      (node (ref "U$1") (pin "15") (pinfunction "15_15") (pintype "bidirectional"))
      (node (ref "U$1") (pin "25") (pinfunction "25_25") (pintype "bidirectional"))
      (node (ref "U$1") (pin "3") (pinfunction "3_3") (pintype "bidirectional"))
      (node (ref "U$1") (pin "37") (pinfunction "37_37") (pintype "bidirectional"))
      (node (ref "U$2") (pin "15") (pinfunction "15_15") (pintype "bidirectional"))
      (node (ref "U$2") (pin "27") (pinfunction "27_27") (pintype "bidirectional"))
      (node (ref "U$2") (pin "3") (pinfunction "3_3") (pintype "bidirectional"))
      (node (ref "U$2") (pin "37") (pinfunction "37_37") (pintype "bidirectional"))
      (node (ref "U$3") (pin "13") (pinfunction "13_13") (pintype "bidirectional"))
      (node (ref "U$3") (pin "27") (pinfunction "27_27") (pintype "bidirectional"))
      (node (ref "U$3") (pin "3") (pinfunction "3_3") (pintype "bidirectional"))
      (node (ref "U$3") (pin "37") (pinfunction "37_37") (pintype "bidirectional"))
      (node (ref "U$4") (pin "15") (pinfunction "15_15") (pintype "bidirectional"))
      (node (ref "U$4") (pin "25") (pinfunction "25_25") (pintype "bidirectional"))
      (node (ref "U$4") (pin "3") (pinfunction "3_3") (pintype "bidirectional"))
      (node (ref "U$4") (pin "37") (pinfunction "37_37") (pintype "bidirectional"))
      (node (ref "USB-UART_1") (pin "1") (pinfunction "1_1") (pintype "passive"))
    )
    (net (code "82") (name "GPIO_IN[0]") (class "Default")
      (node (ref "JP1") (pin "31") (pinfunction "31_31") (pintype "passive"))
      (node (ref "U$4") (pin "11") (pinfunction "11_11") (pintype "bidirectional"))
    )
    (net (code "83") (name "GPIO_IN[1]") (class "Default")
      (node (ref "JP1") (pin "29") (pinfunction "29_29") (pintype "passive"))
      (node (ref "U$4") (pin "14") (pinfunction "14_14") (pintype "bidirectional"))
    )
    (net (code "84") (name "GPIO_IN[2]") (class "Default")
      (node (ref "JP1") (pin "27") (pinfunction "27_27") (pintype "passive"))
      (node (ref "U$4") (pin "16") (pinfunction "16_16") (pintype "bidirectional"))
    )
    (net (code "85") (name "GPIO_IN[3]") (class "Default")
      (node (ref "JP1") (pin "25") (pinfunction "25_25") (pintype "passive"))
      (node (ref "U$4") (pin "18") (pinfunction "18_18") (pintype "bidirectional"))
    )
    (net (code "86") (name "GPIO_IN[4]") (class "Default")
      (node (ref "JP1") (pin "23") (pinfunction "23_23") (pintype "passive"))
      (node (ref "U$4") (pin "28") (pinfunction "28_28") (pintype "bidirectional"))
    )
    (net (code "87") (name "GPIO_IN[5]") (class "Default")
      (node (ref "JP1") (pin "21") (pinfunction "21_21") (pintype "passive"))
      (node (ref "U$4") (pin "30") (pinfunction "30_30") (pintype "bidirectional"))
    )
    (net (code "88") (name "GPIO_IN[6]") (class "Default")
      (node (ref "JP1") (pin "19") (pinfunction "19_19") (pintype "passive"))
      (node (ref "U$4") (pin "29") (pinfunction "29_29") (pintype "bidirectional"))
    )
    (net (code "89") (name "GPIO_IN[7]") (class "Default")
      (node (ref "JP1") (pin "17") (pinfunction "17_17") (pintype "passive"))
      (node (ref "U$4") (pin "32") (pinfunction "32_32") (pintype "bidirectional"))
    )
    (net (code "90") (name "GPIO_IN[8]") (class "Default")
      (node (ref "JP1") (pin "15") (pinfunction "15_15") (pintype "passive"))
      (node (ref "U$4") (pin "31") (pinfunction "31_31") (pintype "bidirectional"))
    )
    (net (code "91") (name "GPIO_IN[9]") (class "Default")
      (node (ref "JP1") (pin "13") (pinfunction "13_13") (pintype "passive"))
      (node (ref "U$4") (pin "34") (pinfunction "34_34") (pintype "bidirectional"))
    )
    (net (code "92") (name "GPIO_IN[10]") (class "Default")
      (node (ref "JP1") (pin "11") (pinfunction "11_11") (pintype "passive"))
      (node (ref "U$4") (pin "33") (pinfunction "33_33") (pintype "bidirectional"))
    )
    (net (code "93") (name "GPIO_IN[11]") (class "Default")
      (node (ref "JP1") (pin "9") (pinfunction "9_9") (pintype "passive"))
      (node (ref "U$4") (pin "36") (pinfunction "36_36") (pintype "bidirectional"))
    )
    (net (code "94") (name "GPIO_IN[12]") (class "Default")
      (node (ref "JP1") (pin "7") (pinfunction "7_7") (pintype "passive"))
      (node (ref "U$4") (pin "35") (pinfunction "35_35") (pintype "bidirectional"))
    )
    (net (code "95") (name "GPIO_IN[13]") (class "Default")
      (node (ref "JP1") (pin "5") (pinfunction "5_5") (pintype "passive"))
      (node (ref "U$4") (pin "38") (pinfunction "38_38") (pintype "bidirectional"))
    )
    (net (code "96") (name "GPIO_IN[14]") (class "Default")
      (node (ref "JP1") (pin "3") (pinfunction "3_3") (pintype "passive"))
      (node (ref "U$4") (pin "40") (pinfunction "40_40") (pintype "bidirectional"))
    )
    (net (code "97") (name "GPIO_IN[15]") (class "Default")
      (node (ref "JP1") (pin "1") (pinfunction "1_1") (pintype "passive"))
      (node (ref "U$4") (pin "42") (pinfunction "42_42") (pintype "bidirectional"))
    )
    (net (code "98") (name "GPIO_JRST_N") (class "Default")
      (node (ref "GPIO_0") (pin "27") (pinfunction "27_27") (pintype "passive"))
      (node (ref "RESET") (pin "4") (pinfunction "4_4") (pintype "passive"))
    )
    (net (code "99") (name "GPIO_OUT[0]") (class "Default")
      (node (ref "LED") (pin "31") (pinfunction "31_31") (pintype "passive"))
      (node (ref "U$3") (pin "12") (pinfunction "12_12") (pintype "bidirectional"))
    )
    (net (code "100") (name "GPIO_OUT[1]") (class "Default")
      (node (ref "LED") (pin "29") (pinfunction "29_29") (pintype "passive"))
      (node (ref "U$3") (pin "11") (pinfunction "11_11") (pintype "bidirectional"))
    )
    (net (code "101") (name "GPIO_OUT[2]") (class "Default")
      (node (ref "LED") (pin "27") (pinfunction "27_27") (pintype "passive"))
      (node (ref "U$3") (pin "14") (pinfunction "14_14") (pintype "bidirectional"))
    )
    (net (code "102") (name "GPIO_OUT[3]") (class "Default")
      (node (ref "LED") (pin "25") (pinfunction "25_25") (pintype "passive"))
      (node (ref "U$3") (pin "16") (pinfunction "16_16") (pintype "bidirectional"))
    )
    (net (code "103") (name "GPIO_OUT[4]") (class "Default")
      (node (ref "LED") (pin "23") (pinfunction "23_23") (pintype "passive"))
      (node (ref "U$3") (pin "18") (pinfunction "18_18") (pintype "bidirectional"))
    )
    (net (code "104") (name "GPIO_OUT[5]") (class "Default")
      (node (ref "LED") (pin "21") (pinfunction "21_21") (pintype "passive"))
      (node (ref "U$3") (pin "28") (pinfunction "28_28") (pintype "bidirectional"))
    )
    (net (code "105") (name "GPIO_OUT[6]") (class "Default")
      (node (ref "LED") (pin "19") (pinfunction "19_19") (pintype "passive"))
      (node (ref "U$3") (pin "30") (pinfunction "30_30") (pintype "bidirectional"))
    )
    (net (code "106") (name "GPIO_OUT[7]") (class "Default")
      (node (ref "LED") (pin "17") (pinfunction "17_17") (pintype "passive"))
      (node (ref "U$3") (pin "29") (pinfunction "29_29") (pintype "bidirectional"))
    )
    (net (code "107") (name "GPIO_OUT[8]") (class "Default")
      (node (ref "LED") (pin "15") (pinfunction "15_15") (pintype "passive"))
      (node (ref "U$3") (pin "32") (pinfunction "32_32") (pintype "bidirectional"))
    )
    (net (code "108") (name "GPIO_OUT[9]") (class "Default")
      (node (ref "LED") (pin "13") (pinfunction "13_13") (pintype "passive"))
      (node (ref "U$3") (pin "31") (pinfunction "31_31") (pintype "bidirectional"))
    )
    (net (code "109") (name "GPIO_OUT[10]") (class "Default")
      (node (ref "LED") (pin "11") (pinfunction "11_11") (pintype "passive"))
      (node (ref "U$3") (pin "34") (pinfunction "34_34") (pintype "bidirectional"))
    )
    (net (code "110") (name "GPIO_OUT[11]") (class "Default")
      (node (ref "LED") (pin "9") (pinfunction "9_9") (pintype "passive"))
      (node (ref "U$3") (pin "33") (pinfunction "33_33") (pintype "bidirectional"))
    )
    (net (code "111") (name "GPIO_OUT[12]") (class "Default")
      (node (ref "LED") (pin "7") (pinfunction "7_7") (pintype "passive"))
      (node (ref "U$3") (pin "36") (pinfunction "36_36") (pintype "bidirectional"))
    )
    (net (code "112") (name "GPIO_OUT[13]") (class "Default")
      (node (ref "LED") (pin "5") (pinfunction "5_5") (pintype "passive"))
      (node (ref "U$3") (pin "35") (pinfunction "35_35") (pintype "bidirectional"))
    )
    (net (code "113") (name "GPIO_OUT[14]") (class "Default")
      (node (ref "LED") (pin "3") (pinfunction "3_3") (pintype "passive"))
      (node (ref "U$3") (pin "38") (pinfunction "38_38") (pintype "bidirectional"))
    )
    (net (code "114") (name "GPIO_OUT[15]") (class "Default")
      (node (ref "LED") (pin "1") (pinfunction "1_1") (pintype "passive"))
      (node (ref "U$3") (pin "40") (pinfunction "40_40") (pintype "bidirectional"))
    )
    (net (code "115") (name "GPIO_RST_N") (class "Default")
      (node (ref "GPIO_1") (pin "15") (pinfunction "15_15") (pintype "passive"))
      (node (ref "RESET") (pin "8") (pinfunction "8_8") (pintype "passive"))
    )
    (net (code "116") (name "IN_3V3") (class "Default")
      (node (ref "C11") (pin "1") (pinfunction "1_1") (pintype "passive"))
      (node (ref "IC7") (pin "1") (pinfunction "IN_1") (pintype "input"))
      (node (ref "VDD_3V3") (pin "2") (pinfunction "2_2") (pintype "passive"))
      (node (ref "VDD_3V3") (pin "4") (pinfunction "4_4") (pintype "passive"))
    )
    (net (code "117") (name "IN_VDD") (class "Default")
      (node (ref "C22") (pin "1") (pinfunction "1_1") (pintype "passive"))
      (node (ref "IC3") (pin "1") (pinfunction "IN_1") (pintype "input"))
      (node (ref "VDD") (pin "2") (pinfunction "2_2") (pintype "passive"))
      (node (ref "VDD") (pin "4") (pinfunction "4_4") (pintype "passive"))
    )
    (net (code "118") (name "IN_VDDO") (class "Default")
      (node (ref "C9") (pin "1") (pinfunction "1_1") (pintype "passive"))
      (node (ref "IC5") (pin "1") (pinfunction "IN_1") (pintype "input"))
      (node (ref "VDDO") (pin "2") (pinfunction "2_2") (pintype "passive"))
      (node (ref "VDDO") (pin "4") (pinfunction "4_4") (pintype "passive"))
    )
    (net (code "119") (name "JTAG_JTAG_TCK") (class "Default")
      (node (ref "JTAG") (pin "5") (pinfunction "5_5") (pintype "passive"))
      (node (ref "U$4") (pin "10") (pinfunction "10_10") (pintype "bidirectional"))
    )
    (net (code "120") (name "JTAG_JTAG_TDI") (class "Default")
      (node (ref "JTAG") (pin "1") (pinfunction "1_1") (pintype "passive"))
      (node (ref "U$4") (pin "12") (pinfunction "12_12") (pintype "bidirectional"))
    )
    (net (code "121") (name "JTAG_JTAG_TDO") (class "Default")
      (node (ref "JTAG") (pin "3") (pinfunction "3_3") (pintype "passive"))
      (node (ref "U$4") (pin "9") (pinfunction "9_9") (pintype "bidirectional"))
    )
    (net (code "122") (name "JTAG_JTAG_TMS") (class "Default")
      (node (ref "JTAG") (pin "7") (pinfunction "7_7") (pintype "passive"))
      (node (ref "U$4") (pin "7") (pinfunction "7_7") (pintype "bidirectional"))
    )
    (net (code "123") (name "JTAG_TCK") (class "Default")
      (node (ref "IC6") (pin "16") (pinfunction "B4_16") (pintype "bidirectional"))
      (node (ref "JTAG_CONNECTOR") (pin "9") (pinfunction "9_9") (pintype "passive"))
    )
    (net (code "124") (name "JTAG_TDI") (class "Default")
      (node (ref "IC6") (pin "18") (pinfunction "B2_18") (pintype "bidirectional"))
      (node (ref "JTAG_CONNECTOR") (pin "5") (pinfunction "5_5") (pintype "passive"))
    )
    (net (code "125") (name "JTAG_TDO") (class "Default")
      (node (ref "IC6") (pin "17") (pinfunction "B3_17") (pintype "bidirectional"))
      (node (ref "JTAG_CONNECTOR") (pin "13") (pinfunction "13_13") (pintype "passive"))
    )
    (net (code "126") (name "JTAG_TMS") (class "Default")
      (node (ref "IC6") (pin "15") (pinfunction "B5_15") (pintype "bidirectional"))
      (node (ref "JTAG_CONNECTOR") (pin "7") (pinfunction "7_7") (pintype "passive"))
    )
    (net (code "127") (name "LED_0") (class "Default")
      (node (ref "LED") (pin "32") (pinfunction "32_32") (pintype "passive"))
      (node (ref "Q9") (pin "1") (pinfunction "G_1") (pintype "bidirectional"))
      (node (ref "R38") (pin "1") (pinfunction "1_1") (pintype "passive"))
    )
    (net (code "128") (name "LED_1") (class "Default")
      (node (ref "LED") (pin "30") (pinfunction "30_30") (pintype "passive"))
      (node (ref "Q10") (pin "1") (pinfunction "G_1") (pintype "bidirectional"))
      (node (ref "R40") (pin "1") (pinfunction "1_1") (pintype "passive"))
    )
    (net (code "129") (name "LED_2") (class "Default")
      (node (ref "LED") (pin "28") (pinfunction "28_28") (pintype "passive"))
      (node (ref "Q1") (pin "1") (pinfunction "G_1") (pintype "bidirectional"))
      (node (ref "R2") (pin "1") (pinfunction "1_1") (pintype "passive"))
    )
    (net (code "130") (name "LED_3") (class "Default")
      (node (ref "LED") (pin "26") (pinfunction "26_26") (pintype "passive"))
      (node (ref "Q2") (pin "1") (pinfunction "G_1") (pintype "bidirectional"))
      (node (ref "R4") (pin "1") (pinfunction "1_1") (pintype "passive"))
    )
    (net (code "131") (name "LED_4") (class "Default")
      (node (ref "LED") (pin "24") (pinfunction "24_24") (pintype "passive"))
      (node (ref "Q5") (pin "1") (pinfunction "G_1") (pintype "bidirectional"))
      (node (ref "R10") (pin "1") (pinfunction "1_1") (pintype "passive"))
    )
    (net (code "132") (name "LED_5") (class "Default")
      (node (ref "LED") (pin "22") (pinfunction "22_22") (pintype "passive"))
      (node (ref "Q6") (pin "1") (pinfunction "G_1") (pintype "bidirectional"))
      (node (ref "R12") (pin "1") (pinfunction "1_1") (pintype "passive"))
    )
    (net (code "133") (name "LED_6") (class "Default")
      (node (ref "LED") (pin "20") (pinfunction "20_20") (pintype "passive"))
      (node (ref "Q13") (pin "1") (pinfunction "G_1") (pintype "bidirectional"))
      (node (ref "R18") (pin "1") (pinfunction "1_1") (pintype "passive"))
    )
    (net (code "134") (name "LED_7") (class "Default")
      (node (ref "LED") (pin "18") (pinfunction "18_18") (pintype "passive"))
      (node (ref "Q14") (pin "1") (pinfunction "G_1") (pintype "bidirectional"))
      (node (ref "R20") (pin "1") (pinfunction "1_1") (pintype "passive"))
    )
    (net (code "135") (name "LED_8") (class "Default")
      (node (ref "LED") (pin "16") (pinfunction "16_16") (pintype "passive"))
      (node (ref "Q11") (pin "1") (pinfunction "G_1") (pintype "bidirectional"))
      (node (ref "R50") (pin "1") (pinfunction "1_1") (pintype "passive"))
    )
    (net (code "136") (name "LED_9") (class "Default")
      (node (ref "LED") (pin "14") (pinfunction "14_14") (pintype "passive"))
      (node (ref "Q12") (pin "1") (pinfunction "G_1") (pintype "bidirectional"))
      (node (ref "R52") (pin "1") (pinfunction "1_1") (pintype "passive"))
    )
    (net (code "137") (name "LED_10") (class "Default")
      (node (ref "LED") (pin "12") (pinfunction "12_12") (pintype "passive"))
      (node (ref "Q3") (pin "1") (pinfunction "G_1") (pintype "bidirectional"))
      (node (ref "R6") (pin "1") (pinfunction "1_1") (pintype "passive"))
    )
    (net (code "138") (name "LED_11") (class "Default")
      (node (ref "LED") (pin "10") (pinfunction "10_10") (pintype "passive"))
      (node (ref "Q4") (pin "1") (pinfunction "G_1") (pintype "bidirectional"))
      (node (ref "R8") (pin "1") (pinfunction "1_1") (pintype "passive"))
    )
    (net (code "139") (name "LED_12") (class "Default")
      (node (ref "LED") (pin "8") (pinfunction "8_8") (pintype "passive"))
      (node (ref "Q7") (pin "1") (pinfunction "G_1") (pintype "bidirectional"))
      (node (ref "R14") (pin "1") (pinfunction "1_1") (pintype "passive"))
    )
    (net (code "140") (name "LED_13") (class "Default")
      (node (ref "LED") (pin "6") (pinfunction "6_6") (pintype "passive"))
      (node (ref "Q8") (pin "1") (pinfunction "G_1") (pintype "bidirectional"))
      (node (ref "R16") (pin "1") (pinfunction "1_1") (pintype "passive"))
    )
    (net (code "141") (name "LED_14") (class "Default")
      (node (ref "LED") (pin "4") (pinfunction "4_4") (pintype "passive"))
      (node (ref "Q15") (pin "1") (pinfunction "G_1") (pintype "bidirectional"))
      (node (ref "R22") (pin "1") (pinfunction "1_1") (pintype "passive"))
    )
    (net (code "142") (name "LED_15") (class "Default")
      (node (ref "LED") (pin "2") (pinfunction "2_2") (pintype "passive"))
      (node (ref "Q16") (pin "1") (pinfunction "G_1") (pintype "bidirectional"))
      (node (ref "R24") (pin "1") (pinfunction "1_1") (pintype "passive"))
    )
    (net (code "143") (name "Net-(C10-Pad2)") (class "Default")
      (node (ref "C10") (pin "2") (pinfunction "2_2") (pintype "passive"))
      (node (ref "R48") (pin "1") (pinfunction "1_1") (pintype "passive"))
    )
    (net (code "144") (name "Net-(C12-Pad2)") (class "Default")
      (node (ref "C12") (pin "2") (pinfunction "2_2") (pintype "passive"))
      (node (ref "R59") (pin "1") (pinfunction "1_1") (pintype "passive"))
    )
    (net (code "145") (name "Net-(C25-Pad2)") (class "Default")
      (node (ref "C25") (pin "2") (pinfunction "2_2") (pintype "passive"))
      (node (ref "R45") (pin "1") (pinfunction "1_1") (pintype "passive"))
    )
    (net (code "146") (name "Net-(IC1-A2)") (class "Default")
      (node (ref "IC1") (pin "3") (pinfunction "A2_3") (pintype "bidirectional"))
      (node (ref "SDCARD") (pin "2") (pinfunction "2_2") (pintype "passive"))
    )
    (net (code "147") (name "Net-(IC1-A3)") (class "Default")
      (node (ref "IC1") (pin "4") (pinfunction "A3_4") (pintype "bidirectional"))
      (node (ref "SDCARD") (pin "4") (pinfunction "4_4") (pintype "passive"))
    )
    (net (code "148") (name "Net-(IC1-A4)") (class "Default")
      (node (ref "IC1") (pin "5") (pinfunction "A4_5") (pintype "bidirectional"))
      (node (ref "SDCARD") (pin "6") (pinfunction "6_6") (pintype "passive"))
    )
    (net (code "149") (name "Net-(IC1-A5)") (class "Default")
      (node (ref "IC1") (pin "6") (pinfunction "A5_6") (pintype "bidirectional"))
      (node (ref "SDCARD") (pin "8") (pinfunction "8_8") (pintype "passive"))
    )
    (net (code "150") (name "Net-(IC2-A3)") (class "Default")
      (node (ref "IC2") (pin "4") (pinfunction "A3_4") (pintype "bidirectional"))
      (node (ref "UART") (pin "2") (pinfunction "2_2") (pintype "passive"))
    )
    (net (code "151") (name "Net-(IC2-A4)") (class "Default")
      (node (ref "IC2") (pin "5") (pinfunction "A4_5") (pintype "bidirectional"))
      (node (ref "UART") (pin "4") (pinfunction "4_4") (pintype "passive"))
    )
    (net (code "152") (name "Net-(IC3-FB)") (class "Default")
      (node (ref "IC3") (pin "4") (pinfunction "FB_4") (pintype "bidirectional"))
      (node (ref "R43") (pin "1") (pinfunction "1_1") (pintype "passive"))
      (node (ref "R44") (pin "2") (pinfunction "2_2") (pintype "passive"))
    )
    (net (code "153") (name "Net-(IC4-A2)") (class "Default")
      (node (ref "IC4") (pin "3") (pinfunction "A2_3") (pintype "bidirectional"))
      (node (ref "QSPI") (pin "2") (pinfunction "2_2") (pintype "passive"))
    )
    (net (code "154") (name "Net-(IC4-A3)") (class "Default")
      (node (ref "IC4") (pin "4") (pinfunction "A3_4") (pintype "bidirectional"))
      (node (ref "QSPI") (pin "4") (pinfunction "4_4") (pintype "passive"))
    )
    (net (code "155") (name "Net-(IC4-A4)") (class "Default")
      (node (ref "IC4") (pin "5") (pinfunction "A4_5") (pintype "bidirectional"))
      (node (ref "QSPI") (pin "6") (pinfunction "6_6") (pintype "passive"))
    )
    (net (code "156") (name "Net-(IC4-A5)") (class "Default")
      (node (ref "IC4") (pin "6") (pinfunction "A5_6") (pintype "bidirectional"))
      (node (ref "QSPI") (pin "8") (pinfunction "8_8") (pintype "passive"))
    )
    (net (code "157") (name "Net-(IC4-A6)") (class "Default")
      (node (ref "IC4") (pin "7") (pinfunction "A6_7") (pintype "bidirectional"))
      (node (ref "QSPI") (pin "10") (pinfunction "10_10") (pintype "passive"))
    )
    (net (code "158") (name "Net-(IC4-A7)") (class "Default")
      (node (ref "IC4") (pin "8") (pinfunction "A7_8") (pintype "bidirectional"))
      (node (ref "QSPI") (pin "12") (pinfunction "12_12") (pintype "passive"))
    )
    (net (code "159") (name "Net-(IC5-FB)") (class "Default")
      (node (ref "IC5") (pin "4") (pinfunction "FB_4") (pintype "bidirectional"))
      (node (ref "R46") (pin "1") (pinfunction "1_1") (pintype "passive"))
      (node (ref "R47") (pin "2") (pinfunction "2_2") (pintype "passive"))
    )
    (net (code "160") (name "Net-(IC6-A2)") (class "Default")
      (node (ref "IC6") (pin "3") (pinfunction "A2_3") (pintype "bidirectional"))
      (node (ref "JTAG") (pin "2") (pinfunction "2_2") (pintype "passive"))
    )
    (net (code "161") (name "Net-(IC6-A3)") (class "Default")
      (node (ref "IC6") (pin "4") (pinfunction "A3_4") (pintype "bidirectional"))
      (node (ref "JTAG") (pin "4") (pinfunction "4_4") (pintype "passive"))
    )
    (net (code "162") (name "Net-(IC6-A4)") (class "Default")
      (node (ref "IC6") (pin "5") (pinfunction "A4_5") (pintype "bidirectional"))
      (node (ref "JTAG") (pin "6") (pinfunction "6_6") (pintype "passive"))
    )
    (net (code "163") (name "Net-(IC6-A5)") (class "Default")
      (node (ref "IC6") (pin "6") (pinfunction "A5_6") (pintype "bidirectional"))
      (node (ref "JTAG") (pin "8") (pinfunction "8_8") (pintype "passive"))
    )
    (net (code "164") (name "Net-(IC7-FB)") (class "Default")
      (node (ref "IC7") (pin "4") (pinfunction "FB_4") (pintype "bidirectional"))
      (node (ref "R57") (pin "1") (pinfunction "1_1") (pintype "passive"))
      (node (ref "R58") (pin "2") (pinfunction "2_2") (pintype "passive"))
    )
    (net (code "165") (name "Net-(JP1-Pad2)") (class "Default")
      (node (ref "JP1") (pin "2") (pinfunction "2_2") (pintype "passive"))
      (node (ref "R32") (pin "2") (pinfunction "2_2") (pintype "passive"))
      (node (ref "S1") (pin "1") (pinfunction "1_1") (pintype "bidirectional"))
    )
    (net (code "166") (name "Net-(JP1-Pad4)") (class "Default")
      (node (ref "JP1") (pin "4") (pinfunction "4_4") (pintype "passive"))
      (node (ref "R31") (pin "2") (pinfunction "2_2") (pintype "passive"))
      (node (ref "S1") (pin "2") (pinfunction "2_2") (pintype "bidirectional"))
    )
    (net (code "167") (name "Net-(JP1-Pad6)") (class "Default")
      (node (ref "JP1") (pin "6") (pinfunction "6_6") (pintype "passive"))
      (node (ref "R30") (pin "2") (pinfunction "2_2") (pintype "passive"))
      (node (ref "S1") (pin "3") (pinfunction "3_3") (pintype "bidirectional"))
    )
    (net (code "168") (name "Net-(JP1-Pad8)") (class "Default")
      (node (ref "JP1") (pin "8") (pinfunction "8_8") (pintype "passive"))
      (node (ref "R29") (pin "2") (pinfunction "2_2") (pintype "passive"))
      (node (ref "S1") (pin "4") (pinfunction "4_4") (pintype "bidirectional"))
    )
    (net (code "169") (name "Net-(JP1-Pad10)") (class "Default")
      (node (ref "JP1") (pin "10") (pinfunction "10_10") (pintype "passive"))
      (node (ref "R28") (pin "2") (pinfunction "2_2") (pintype "passive"))
      (node (ref "S1") (pin "5") (pinfunction "5_5") (pintype "bidirectional"))
    )
    (net (code "170") (name "Net-(JP1-Pad12)") (class "Default")
      (node (ref "JP1") (pin "12") (pinfunction "12_12") (pintype "passive"))
      (node (ref "R27") (pin "2") (pinfunction "2_2") (pintype "passive"))
      (node (ref "S1") (pin "6") (pinfunction "6_6") (pintype "bidirectional"))
    )
    (net (code "171") (name "Net-(JP1-Pad14)") (class "Default")
      (node (ref "JP1") (pin "14") (pinfunction "14_14") (pintype "passive"))
      (node (ref "R26") (pin "2") (pinfunction "2_2") (pintype "passive"))
      (node (ref "S1") (pin "7") (pinfunction "7_7") (pintype "bidirectional"))
    )
    (net (code "172") (name "Net-(JP1-Pad16)") (class "Default")
      (node (ref "JP1") (pin "16") (pinfunction "16_16") (pintype "passive"))
      (node (ref "R25") (pin "2") (pinfunction "2_2") (pintype "passive"))
      (node (ref "S1") (pin "8") (pinfunction "8_8") (pintype "bidirectional"))
    )
    (net (code "173") (name "Net-(JP1-Pad18)") (class "Default")
      (node (ref "JP1") (pin "18") (pinfunction "18_18") (pintype "passive"))
      (node (ref "R56") (pin "2") (pinfunction "2_2") (pintype "passive"))
      (node (ref "S2") (pin "1") (pinfunction "1_1") (pintype "bidirectional"))
    )
    (net (code "174") (name "Net-(JP1-Pad20)") (class "Default")
      (node (ref "JP1") (pin "20") (pinfunction "20_20") (pintype "passive"))
      (node (ref "R55") (pin "2") (pinfunction "2_2") (pintype "passive"))
      (node (ref "S2") (pin "2") (pinfunction "2_2") (pintype "bidirectional"))
    )
    (net (code "175") (name "Net-(JP1-Pad22)") (class "Default")
      (node (ref "JP1") (pin "22") (pinfunction "22_22") (pintype "passive"))
      (node (ref "R54") (pin "2") (pinfunction "2_2") (pintype "passive"))
      (node (ref "S2") (pin "3") (pinfunction "3_3") (pintype "bidirectional"))
    )
    (net (code "176") (name "Net-(JP1-Pad24)") (class "Default")
      (node (ref "JP1") (pin "24") (pinfunction "24_24") (pintype "passive"))
      (node (ref "R53") (pin "2") (pinfunction "2_2") (pintype "passive"))
      (node (ref "S2") (pin "4") (pinfunction "4_4") (pintype "bidirectional"))
    )
    (net (code "177") (name "Net-(JP1-Pad26)") (class "Default")
      (node (ref "JP1") (pin "26") (pinfunction "26_26") (pintype "passive"))
      (node (ref "R36") (pin "2") (pinfunction "2_2") (pintype "passive"))
      (node (ref "S2") (pin "5") (pinfunction "5_5") (pintype "bidirectional"))
    )
    (net (code "178") (name "Net-(JP1-Pad28)") (class "Default")
      (node (ref "JP1") (pin "28") (pinfunction "28_28") (pintype "passive"))
      (node (ref "R35") (pin "2") (pinfunction "2_2") (pintype "passive"))
      (node (ref "S2") (pin "6") (pinfunction "6_6") (pintype "bidirectional"))
    )
    (net (code "179") (name "Net-(JP1-Pad30)") (class "Default")
      (node (ref "JP1") (pin "30") (pinfunction "30_30") (pintype "passive"))
      (node (ref "R34") (pin "2") (pinfunction "2_2") (pintype "passive"))
      (node (ref "S2") (pin "7") (pinfunction "7_7") (pintype "bidirectional"))
    )
    (net (code "180") (name "Net-(JP1-Pad32)") (class "Default")
      (node (ref "JP1") (pin "32") (pinfunction "32_32") (pintype "passive"))
      (node (ref "R33") (pin "2") (pinfunction "2_2") (pintype "passive"))
      (node (ref "S2") (pin "8") (pinfunction "8_8") (pintype "bidirectional"))
    )
    (net (code "181") (name "Net-(LED1-PadA)") (class "Default")
      (node (ref "LED1") (pin "A") (pinfunction "A_A") (pintype "passive"))
      (node (ref "R1") (pin "1") (pinfunction "1_1") (pintype "passive"))
    )
    (net (code "182") (name "Net-(LED2-PadA)") (class "Default")
      (node (ref "LED2") (pin "A") (pinfunction "A_A") (pintype "passive"))
      (node (ref "R3") (pin "1") (pinfunction "1_1") (pintype "passive"))
    )
    (net (code "183") (name "Net-(LED3-PadA)") (class "Default")
      (node (ref "LED3") (pin "A") (pinfunction "A_A") (pintype "passive"))
      (node (ref "R5") (pin "1") (pinfunction "1_1") (pintype "passive"))
    )
    (net (code "184") (name "Net-(LED4-PadA)") (class "Default")
      (node (ref "LED4") (pin "A") (pinfunction "A_A") (pintype "passive"))
      (node (ref "R7") (pin "1") (pinfunction "1_1") (pintype "passive"))
    )
    (net (code "185") (name "Net-(LED5-PadA)") (class "Default")
      (node (ref "LED5") (pin "A") (pinfunction "A_A") (pintype "passive"))
      (node (ref "R9") (pin "1") (pinfunction "1_1") (pintype "passive"))
    )
    (net (code "186") (name "Net-(LED6-PadA)") (class "Default")
      (node (ref "LED6") (pin "A") (pinfunction "A_A") (pintype "passive"))
      (node (ref "R11") (pin "1") (pinfunction "1_1") (pintype "passive"))
    )
    (net (code "187") (name "Net-(LED7-PadA)") (class "Default")
      (node (ref "LED7") (pin "A") (pinfunction "A_A") (pintype "passive"))
      (node (ref "R13") (pin "1") (pinfunction "1_1") (pintype "passive"))
    )
    (net (code "188") (name "Net-(LED8-PadA)") (class "Default")
      (node (ref "LED8") (pin "A") (pinfunction "A_A") (pintype "passive"))
      (node (ref "R15") (pin "1") (pinfunction "1_1") (pintype "passive"))
    )
    (net (code "189") (name "Net-(LED9-PadA)") (class "Default")
      (node (ref "LED9") (pin "A") (pinfunction "A_A") (pintype "passive"))
      (node (ref "R37") (pin "1") (pinfunction "1_1") (pintype "passive"))
    )
    (net (code "190") (name "Net-(LED10-PadA)") (class "Default")
      (node (ref "LED10") (pin "A") (pinfunction "A_A") (pintype "passive"))
      (node (ref "R39") (pin "1") (pinfunction "1_1") (pintype "passive"))
    )
    (net (code "191") (name "Net-(LED11-PadA)") (class "Default")
      (node (ref "LED11") (pin "A") (pinfunction "A_A") (pintype "passive"))
      (node (ref "R49") (pin "1") (pinfunction "1_1") (pintype "passive"))
    )
    (net (code "192") (name "Net-(LED12-PadA)") (class "Default")
      (node (ref "LED12") (pin "A") (pinfunction "A_A") (pintype "passive"))
      (node (ref "R51") (pin "1") (pinfunction "1_1") (pintype "passive"))
    )
    (net (code "193") (name "Net-(LED13-PadA)") (class "Default")
      (node (ref "LED13") (pin "A") (pinfunction "A_A") (pintype "passive"))
      (node (ref "R60") (pin "1") (pinfunction "1_1") (pintype "passive"))
    )
    (net (code "194") (name "Net-(LED14-PadA)") (class "Default")
      (node (ref "LED14") (pin "A") (pinfunction "A_A") (pintype "passive"))
      (node (ref "R17") (pin "1") (pinfunction "1_1") (pintype "passive"))
    )
    (net (code "195") (name "Net-(LED15-PadA)") (class "Default")
      (node (ref "LED15") (pin "A") (pinfunction "A_A") (pintype "passive"))
      (node (ref "R19") (pin "1") (pinfunction "1_1") (pintype "passive"))
    )
    (net (code "196") (name "Net-(LED16-PadA)") (class "Default")
      (node (ref "LED16") (pin "A") (pinfunction "A_A") (pintype "passive"))
      (node (ref "R21") (pin "1") (pinfunction "1_1") (pintype "passive"))
    )
    (net (code "197") (name "Net-(LED17-PadA)") (class "Default")
      (node (ref "LED17") (pin "A") (pinfunction "A_A") (pintype "passive"))
      (node (ref "R23") (pin "1") (pinfunction "1_1") (pintype "passive"))
    )
    (net (code "198") (name "Net-(LED18-PadA)") (class "Default")
      (node (ref "LED18") (pin "A") (pinfunction "A_A") (pintype "passive"))
      (node (ref "R62") (pin "1") (pinfunction "1_1") (pintype "passive"))
    )
    (net (code "199") (name "Net-(LED19-PadA)") (class "Default")
      (node (ref "LED19") (pin "A") (pinfunction "A_A") (pintype "passive"))
      (node (ref "R64") (pin "1") (pinfunction "1_1") (pintype "passive"))
    )
    (net (code "200") (name "Net-(LED20-PadA)") (class "Default")
      (node (ref "LED20") (pin "A") (pinfunction "A_A") (pintype "passive"))
      (node (ref "R66") (pin "1") (pinfunction "1_1") (pintype "passive"))
    )
    (net (code "201") (name "Net-(LED21-PadA)") (class "Default")
      (node (ref "LED21") (pin "A") (pinfunction "A_A") (pintype "passive"))
      (node (ref "R68") (pin "1") (pinfunction "1_1") (pintype "passive"))
    )
    (net (code "202") (name "Net-(Q1-D)") (class "Default")
      (node (ref "LED1") (pin "C") (pinfunction "C_C") (pintype "passive"))
      (node (ref "Q1") (pin "3") (pinfunction "D_3") (pintype "bidirectional"))
    )
    (net (code "203") (name "Net-(Q2-D)") (class "Default")
      (node (ref "LED2") (pin "C") (pinfunction "C_C") (pintype "passive"))
      (node (ref "Q2") (pin "3") (pinfunction "D_3") (pintype "bidirectional"))
    )
    (net (code "204") (name "Net-(Q3-D)") (class "Default")
      (node (ref "LED3") (pin "C") (pinfunction "C_C") (pintype "passive"))
      (node (ref "Q3") (pin "3") (pinfunction "D_3") (pintype "bidirectional"))
    )
    (net (code "205") (name "Net-(Q4-D)") (class "Default")
      (node (ref "LED4") (pin "C") (pinfunction "C_C") (pintype "passive"))
      (node (ref "Q4") (pin "3") (pinfunction "D_3") (pintype "bidirectional"))
    )
    (net (code "206") (name "Net-(Q5-D)") (class "Default")
      (node (ref "LED5") (pin "C") (pinfunction "C_C") (pintype "passive"))
      (node (ref "Q5") (pin "3") (pinfunction "D_3") (pintype "bidirectional"))
    )
    (net (code "207") (name "Net-(Q6-D)") (class "Default")
      (node (ref "LED6") (pin "C") (pinfunction "C_C") (pintype "passive"))
      (node (ref "Q6") (pin "3") (pinfunction "D_3") (pintype "bidirectional"))
    )
    (net (code "208") (name "Net-(Q7-D)") (class "Default")
      (node (ref "LED7") (pin "C") (pinfunction "C_C") (pintype "passive"))
      (node (ref "Q7") (pin "3") (pinfunction "D_3") (pintype "bidirectional"))
    )
    (net (code "209") (name "Net-(Q8-D)") (class "Default")
      (node (ref "LED8") (pin "C") (pinfunction "C_C") (pintype "passive"))
      (node (ref "Q8") (pin "3") (pinfunction "D_3") (pintype "bidirectional"))
    )
    (net (code "210") (name "Net-(Q9-D)") (class "Default")
      (node (ref "LED9") (pin "C") (pinfunction "C_C") (pintype "passive"))
      (node (ref "Q9") (pin "3") (pinfunction "D_3") (pintype "bidirectional"))
    )
    (net (code "211") (name "Net-(Q10-D)") (class "Default")
      (node (ref "LED10") (pin "C") (pinfunction "C_C") (pintype "passive"))
      (node (ref "Q10") (pin "3") (pinfunction "D_3") (pintype "bidirectional"))
    )
    (net (code "212") (name "Net-(Q11-D)") (class "Default")
      (node (ref "LED11") (pin "C") (pinfunction "C_C") (pintype "passive"))
      (node (ref "Q11") (pin "3") (pinfunction "D_3") (pintype "bidirectional"))
    )
    (net (code "213") (name "Net-(Q12-D)") (class "Default")
      (node (ref "LED12") (pin "C") (pinfunction "C_C") (pintype "passive"))
      (node (ref "Q12") (pin "3") (pinfunction "D_3") (pintype "bidirectional"))
    )
    (net (code "214") (name "Net-(Q13-D)") (class "Default")
      (node (ref "LED14") (pin "C") (pinfunction "C_C") (pintype "passive"))
      (node (ref "Q13") (pin "3") (pinfunction "D_3") (pintype "bidirectional"))
    )
    (net (code "215") (name "Net-(Q14-D)") (class "Default")
      (node (ref "LED15") (pin "C") (pinfunction "C_C") (pintype "passive"))
      (node (ref "Q14") (pin "3") (pinfunction "D_3") (pintype "bidirectional"))
    )
    (net (code "216") (name "Net-(Q15-D)") (class "Default")
      (node (ref "LED16") (pin "C") (pinfunction "C_C") (pintype "passive"))
      (node (ref "Q15") (pin "3") (pinfunction "D_3") (pintype "bidirectional"))
    )
    (net (code "217") (name "Net-(Q16-D)") (class "Default")
      (node (ref "LED17") (pin "C") (pinfunction "C_C") (pintype "passive"))
      (node (ref "Q16") (pin "3") (pinfunction "D_3") (pintype "bidirectional"))
    )
    (net (code "218") (name "Net-(Q17-D)") (class "Default")
      (node (ref "LED13") (pin "C") (pinfunction "C_C") (pintype "passive"))
      (node (ref "Q17") (pin "3") (pinfunction "D_3") (pintype "bidirectional"))
    )
    (net (code "219") (name "Net-(Q18-D)") (class "Default")
      (node (ref "LED18") (pin "C") (pinfunction "C_C") (pintype "passive"))
      (node (ref "Q18") (pin "3") (pinfunction "D_3") (pintype "bidirectional"))
    )
    (net (code "220") (name "Net-(Q19-D)") (class "Default")
      (node (ref "LED19") (pin "C") (pinfunction "C_C") (pintype "passive"))
      (node (ref "Q19") (pin "3") (pinfunction "D_3") (pintype "bidirectional"))
    )
    (net (code "221") (name "Net-(Q20-D)") (class "Default")
      (node (ref "LED20") (pin "C") (pinfunction "C_C") (pintype "passive"))
      (node (ref "Q20") (pin "3") (pinfunction "D_3") (pintype "bidirectional"))
    )
    (net (code "222") (name "Net-(Q21-D)") (class "Default")
      (node (ref "LED21") (pin "C") (pinfunction "C_C") (pintype "passive"))
      (node (ref "Q21") (pin "3") (pinfunction "D_3") (pintype "bidirectional"))
    )
    (net (code "223") (name "Net-(S17-ON_1)") (class "Default")
      (node (ref "R41") (pin "1") (pinfunction "1_1") (pintype "passive"))
      (node (ref "S17") (pin "1") (pinfunction "ON_1_1") (pintype "bidirectional"))
    )
    (net (code "224") (name "Net-(S18-ON_1)") (class "Default")
      (node (ref "R42") (pin "1") (pinfunction "1_1") (pintype "passive"))
      (node (ref "S18") (pin "1") (pinfunction "ON_1_1") (pintype "bidirectional"))
    )
    (net (code "225") (name "OUT_VDD") (class "Default")
      (node (ref "C25") (pin "1") (pinfunction "1_1") (pintype "passive"))
      (node (ref "IC3") (pin "5") (pinfunction "OUT_5") (pintype "output"))
      (node (ref "POWER") (pin "1") (pinfunction "1_1") (pintype "passive"))
      (node (ref "R44") (pin "1") (pinfunction "1_1") (pintype "passive"))
    )
    (net (code "226") (name "OUT_VDDO") (class "Default")
      (node (ref "C10") (pin "1") (pinfunction "1_1") (pintype "passive"))
      (node (ref "IC5") (pin "5") (pinfunction "OUT_5") (pintype "output"))
      (node (ref "POWER") (pin "5") (pinfunction "5_5") (pintype "passive"))
      (node (ref "R47") (pin "1") (pinfunction "1_1") (pintype "passive"))
    )
    (net (code "227") (name "OUT_VDD_3V3") (class "Default")
      (node (ref "C12") (pin "1") (pinfunction "1_1") (pintype "passive"))
      (node (ref "IC7") (pin "5") (pinfunction "OUT_5") (pintype "output"))
      (node (ref "POWER") (pin "9") (pinfunction "9_9") (pintype "passive"))
      (node (ref "R58") (pin "1") (pinfunction "1_1") (pintype "passive"))
    )
    (net (code "228") (name "QSPI_CS") (class "Default")
      (node (ref "FLASH_CONNECTOR") (pin "12") (pinfunction "12_12") (pintype "passive"))
      (node (ref "IC4") (pin "18") (pinfunction "B2_18") (pintype "bidirectional"))
    )
    (net (code "229") (name "QSPI_HOLD") (class "Default")
      (node (ref "FLASH_CONNECTOR") (pin "7") (pinfunction "7_7") (pintype "passive"))
      (node (ref "IC4") (pin "13") (pinfunction "B7_13") (pintype "bidirectional"))
    )
    (net (code "230") (name "QSPI_MISO") (class "Default")
      (node (ref "FLASH_CONNECTOR") (pin "8") (pinfunction "8_8") (pintype "passive"))
      (node (ref "IC4") (pin "16") (pinfunction "B4_16") (pintype "bidirectional"))
    )
    (net (code "231") (name "QSPI_MOSI") (class "Default")
      (node (ref "FLASH_CONNECTOR") (pin "10") (pinfunction "10_10") (pintype "passive"))
      (node (ref "IC4") (pin "15") (pinfunction "B5_15") (pintype "bidirectional"))
    )
    (net (code "232") (name "QSPI_QSPI_CS") (class "Default")
      (node (ref "QSPI") (pin "1") (pinfunction "1_1") (pintype "passive"))
      (node (ref "U$2") (pin "8") (pinfunction "8_8") (pintype "bidirectional"))
    )
    (net (code "233") (name "QSPI_QSPI_HOLD") (class "Default")
      (node (ref "QSPI") (pin "11") (pinfunction "11_11") (pintype "passive"))
      (node (ref "U$1") (pin "40") (pinfunction "40_40") (pintype "bidirectional"))
    )
    (net (code "234") (name "QSPI_QSPI_MISO") (class "Default")
      (node (ref "QSPI") (pin "5") (pinfunction "5_5") (pintype "passive"))
      (node (ref "U$2") (pin "6") (pinfunction "6_6") (pintype "bidirectional"))
    )
    (net (code "235") (name "QSPI_QSPI_MOSI") (class "Default")
      (node (ref "QSPI") (pin "7") (pinfunction "7_7") (pintype "passive"))
      (node (ref "U$2") (pin "4") (pinfunction "4_4") (pintype "bidirectional"))
    )
    (net (code "236") (name "QSPI_QSPI_SCK") (class "Default")
      (node (ref "QSPI") (pin "3") (pinfunction "3_3") (pintype "passive"))
      (node (ref "U$2") (pin "5") (pinfunction "5_5") (pintype "bidirectional"))
    )
    (net (code "237") (name "QSPI_QSPI_WP") (class "Default")
      (node (ref "QSPI") (pin "9") (pinfunction "9_9") (pintype "passive"))
      (node (ref "U$1") (pin "42") (pinfunction "42_42") (pintype "bidirectional"))
    )
    (net (code "238") (name "QSPI_SCK") (class "Default")
      (node (ref "FLASH_CONNECTOR") (pin "6") (pinfunction "6_6") (pintype "passive"))
      (node (ref "IC4") (pin "17") (pinfunction "B3_17") (pintype "bidirectional"))
    )
    (net (code "239") (name "QSPI_WP") (class "Default")
      (node (ref "FLASH_CONNECTOR") (pin "5") (pinfunction "5_5") (pintype "passive"))
      (node (ref "IC4") (pin "14") (pinfunction "B6_14") (pintype "bidirectional"))
    )
    (net (code "240") (name "RX") (class "Default")
      (node (ref "IC2") (pin "16") (pinfunction "B4_16") (pintype "bidirectional"))
      (node (ref "USB-UART_1") (pin "2") (pinfunction "2_2") (pintype "passive"))
    )
    (net (code "241") (name "SDIO_SDIO_CLK") (class "Default")
      (node (ref "SDCARD") (pin "1") (pinfunction "1_1") (pintype "passive"))
      (node (ref "U$4") (pin "8") (pinfunction "8_8") (pintype "bidirectional"))
    )
    (net (code "242") (name "SDIO_SDIO_CMD") (class "Default")
      (node (ref "SDCARD") (pin "3") (pinfunction "3_3") (pintype "passive"))
      (node (ref "U$4") (pin "5") (pinfunction "5_5") (pintype "bidirectional"))
    )
    (net (code "243") (name "SDIO_SDIO_DAT_0") (class "Default")
      (node (ref "SDCARD") (pin "5") (pinfunction "5_5") (pintype "passive"))
      (node (ref "U$4") (pin "6") (pinfunction "6_6") (pintype "bidirectional"))
    )
    (net (code "244") (name "SDIO_SDIO_DAT_3") (class "Default")
      (node (ref "SDCARD") (pin "7") (pinfunction "7_7") (pintype "passive"))
      (node (ref "U$4") (pin "4") (pinfunction "4_4") (pintype "bidirectional"))
    )
    (net (code "245") (name "SD_CLK") (class "Default")
      (node (ref "IC1") (pin "18") (pinfunction "B2_18") (pintype "bidirectional"))
      (node (ref "SDCARD_CONNECTOR") (pin "6") (pinfunction "6_6") (pintype "passive"))
    )
    (net (code "246") (name "SD_CMD") (class "Default")
      (node (ref "IC1") (pin "17") (pinfunction "B3_17") (pintype "bidirectional"))
      (node (ref "SDCARD_CONNECTOR") (pin "10") (pinfunction "10_10") (pintype "passive"))
    )
    (net (code "247") (name "SD_DAT0") (class "Default")
      (node (ref "IC1") (pin "16") (pinfunction "B4_16") (pintype "bidirectional"))
      (node (ref "SDCARD_CONNECTOR") (pin "8") (pinfunction "8_8") (pintype "passive"))
    )
    (net (code "248") (name "SD_DAT3") (class "Default")
      (node (ref "IC1") (pin "15") (pinfunction "B5_15") (pintype "bidirectional"))
      (node (ref "SDCARD_CONNECTOR") (pin "12") (pinfunction "12_12") (pintype "passive"))
    )
    (net (code "249") (name "SW_JRST_N") (class "Default")
      (node (ref "RESET") (pin "2") (pinfunction "2_2") (pintype "passive"))
      (node (ref "S18") (pin "2") (pinfunction "COM_2") (pintype "bidirectional"))
    )
    (net (code "250") (name "SW_RST_N") (class "Default")
      (node (ref "RESET") (pin "6") (pinfunction "6_6") (pintype "passive"))
      (node (ref "S17") (pin "2") (pinfunction "COM_2") (pintype "bidirectional"))
    )
    (net (code "251") (name "TX") (class "Default")
      (node (ref "IC2") (pin "17") (pinfunction "B3_17") (pintype "bidirectional"))
      (node (ref "USB-UART_1") (pin "4") (pinfunction "4_4") (pintype "passive"))
    )
    (net (code "252") (name "UART_RXD") (class "Default")
      (node (ref "U$1") (pin "35") (pinfunction "35_35") (pintype "bidirectional"))
      (node (ref "UART") (pin "3") (pinfunction "3_3") (pintype "passive"))
    )
    (net (code "253") (name "UART_TXD") (class "Default")
      (node (ref "U$1") (pin "38") (pinfunction "38_38") (pintype "bidirectional"))
      (node (ref "UART") (pin "1") (pinfunction "1_1") (pintype "passive"))
    )
    (net (code "254") (name "VCC_GPIO_0") (class "Default")
      (node (ref "GPIO_0") (pin "29") (pinfunction "29_29") (pintype "passive"))
      (node (ref "POWER") (pin "7") (pinfunction "7_7") (pintype "passive"))
    )
    (net (code "255") (name "VCC_GPIO_1") (class "Default")
      (node (ref "GPIO_1") (pin "29") (pinfunction "29_29") (pintype "passive"))
      (node (ref "POWER") (pin "3") (pinfunction "3_3") (pintype "passive"))
    )
    (net (code "256") (name "VCC_GPIO_2") (class "Default")
      (node (ref "GPIO_2") (pin "29") (pinfunction "29_29") (pintype "passive"))
      (node (ref "POWER") (pin "11") (pinfunction "11_11") (pintype "passive"))
    )
    (net (code "257") (name "VCC_GPIO_3") (class "Default")
      (node (ref "GPIO_3") (pin "29") (pinfunction "29_29") (pintype "passive"))
    )
    (net (code "258") (name "VDD") (class "Default")
      (node (ref "C13") (pin "1") (pinfunction "1_1") (pintype "passive"))
      (node (ref "C14") (pin "1") (pinfunction "1_1") (pintype "passive"))
      (node (ref "C15") (pin "1") (pinfunction "1_1") (pintype "passive"))
      (node (ref "C16") (pin "1") (pinfunction "1_1") (pintype "passive"))
      (node (ref "C17") (pin "1") (pinfunction "1_1") (pintype "passive"))
      (node (ref "C18") (pin "1") (pinfunction "1_1") (pintype "passive"))
      (node (ref "C19") (pin "1") (pinfunction "1_1") (pintype "passive"))
      (node (ref "C20") (pin "1") (pinfunction "1_1") (pintype "passive"))
      (node (ref "C21") (pin "1") (pinfunction "1_1") (pintype "passive"))
      (node (ref "C23") (pin "1") (pinfunction "1_1") (pintype "passive"))
      (node (ref "C24") (pin "1") (pinfunction "1_1") (pintype "passive"))
      (node (ref "C26") (pin "1") (pinfunction "1_1") (pintype "passive"))
      (node (ref "C27") (pin "1") (pinfunction "1_1") (pintype "passive"))
      (node (ref "C28") (pin "1") (pinfunction "1_1") (pintype "passive"))
      (node (ref "C29") (pin "1") (pinfunction "1_1") (pintype "passive"))
      (node (ref "C30") (pin "1") (pinfunction "1_1") (pintype "passive"))
      (node (ref "POWER") (pin "2") (pinfunction "2_2") (pintype "passive"))
      (node (ref "POWER") (pin "4") (pinfunction "4_4") (pintype "passive"))
      (node (ref "Q17") (pin "1") (pinfunction "G_1") (pintype "bidirectional"))
      (node (ref "R61") (pin "1") (pinfunction "1_1") (pintype "passive"))
      (node (ref "U$1") (pin "13") (pinfunction "13_13") (pintype "bidirectional"))
      (node (ref "U$1") (pin "39") (pinfunction "39_39") (pintype "bidirectional"))
      (node (ref "U$2") (pin "13") (pinfunction "13_13") (pintype "bidirectional"))
      (node (ref "U$2") (pin "39") (pinfunction "39_39") (pintype "bidirectional"))
      (node (ref "U$3") (pin "15") (pinfunction "15_15") (pintype "bidirectional"))
      (node (ref "U$3") (pin "39") (pinfunction "39_39") (pintype "bidirectional"))
      (node (ref "U$4") (pin "13") (pinfunction "13_13") (pintype "bidirectional"))
      (node (ref "U$4") (pin "39") (pinfunction "39_39") (pintype "bidirectional"))
    )
    (net (code "259") (name "VDDO") (class "Default")
      (node (ref "C1") (pin "1") (pinfunction "1_1") (pintype "passive"))
      (node (ref "C3") (pin "1") (pinfunction "1_1") (pintype "passive"))
      (node (ref "C5") (pin "1") (pinfunction "1_1") (pintype "passive"))
      (node (ref "C7") (pin "1") (pinfunction "1_1") (pintype "passive"))
      (node (ref "IC1") (pin "10") (pinfunction "OE_10") (pintype "bidirectional"))
      (node (ref "IC1") (pin "2") (pinfunction "VCCA_2") (pintype "bidirectional"))
      (node (ref "IC2") (pin "10") (pinfunction "OE_10") (pintype "bidirectional"))
      (node (ref "IC2") (pin "2") (pinfunction "VCCA_2") (pintype "bidirectional"))
      (node (ref "IC4") (pin "10") (pinfunction "OE_10") (pintype "bidirectional"))
      (node (ref "IC4") (pin "2") (pinfunction "VCCA_2") (pintype "bidirectional"))
      (node (ref "IC6") (pin "10") (pinfunction "OE_10") (pintype "bidirectional"))
      (node (ref "IC6") (pin "2") (pinfunction "VCCA_2") (pintype "bidirectional"))
      (node (ref "POWER") (pin "6") (pinfunction "6_6") (pintype "passive"))
      (node (ref "POWER") (pin "8") (pinfunction "8_8") (pintype "passive"))
      (node (ref "Q18") (pin "1") (pinfunction "G_1") (pintype "bidirectional"))
      (node (ref "R63") (pin "1") (pinfunction "1_1") (pintype "passive"))
      (node (ref "U$1") (pin "1") (pinfunction "1_1") (pintype "bidirectional"))
      (node (ref "U$1") (pin "27") (pinfunction "27_27") (pintype "bidirectional"))
      (node (ref "U$2") (pin "1") (pinfunction "1_1") (pintype "bidirectional"))
      (node (ref "U$2") (pin "25") (pinfunction "25_25") (pintype "bidirectional"))
      (node (ref "U$3") (pin "1") (pinfunction "1_1") (pintype "bidirectional"))
      (node (ref "U$3") (pin "25") (pinfunction "25_25") (pintype "bidirectional"))
      (node (ref "U$4") (pin "1") (pinfunction "1_1") (pintype "bidirectional"))
      (node (ref "U$4") (pin "27") (pinfunction "27_27") (pintype "bidirectional"))
    )
    (net (code "260") (name "VDD_3V3") (class "Default")
      (node (ref "C2") (pin "1") (pinfunction "1_1") (pintype "passive"))
      (node (ref "C4") (pin "1") (pinfunction "1_1") (pintype "passive"))
      (node (ref "C6") (pin "1") (pinfunction "1_1") (pintype "passive"))
      (node (ref "C8") (pin "1") (pinfunction "1_1") (pintype "passive"))
      (node (ref "FLASH_CONNECTOR") (pin "1") (pinfunction "1_1") (pintype "passive"))
      (node (ref "FLASH_CONNECTOR") (pin "2") (pinfunction "2_2") (pintype "passive"))
      (node (ref "IC1") (pin "19") (pinfunction "VCCB_19") (pintype "bidirectional"))
      (node (ref "IC2") (pin "19") (pinfunction "VCCB_19") (pintype "bidirectional"))
      (node (ref "IC4") (pin "19") (pinfunction "VCCB_19") (pintype "bidirectional"))
      (node (ref "IC6") (pin "19") (pinfunction "VCCB_19") (pintype "bidirectional"))
      (node (ref "JTAG_CONNECTOR") (pin "1") (pinfunction "1_1") (pintype "passive"))
      (node (ref "JTAG_CONNECTOR") (pin "2") (pinfunction "2_2") (pintype "passive"))
      (node (ref "POWER") (pin "10") (pinfunction "10_10") (pintype "passive"))
      (node (ref "POWER") (pin "12") (pinfunction "12_12") (pintype "passive"))
      (node (ref "Q19") (pin "1") (pinfunction "G_1") (pintype "bidirectional"))
      (node (ref "R1") (pin "2") (pinfunction "2_2") (pintype "passive"))
      (node (ref "R11") (pin "2") (pinfunction "2_2") (pintype "passive"))
      (node (ref "R13") (pin "2") (pinfunction "2_2") (pintype "passive"))
      (node (ref "R15") (pin "2") (pinfunction "2_2") (pintype "passive"))
      (node (ref "R17") (pin "2") (pinfunction "2_2") (pintype "passive"))
      (node (ref "R19") (pin "2") (pinfunction "2_2") (pintype "passive"))
      (node (ref "R21") (pin "2") (pinfunction "2_2") (pintype "passive"))
      (node (ref "R23") (pin "2") (pinfunction "2_2") (pintype "passive"))
      (node (ref "R25") (pin "1") (pinfunction "1_1") (pintype "passive"))
      (node (ref "R26") (pin "1") (pinfunction "1_1") (pintype "passive"))
      (node (ref "R27") (pin "1") (pinfunction "1_1") (pintype "passive"))
      (node (ref "R28") (pin "1") (pinfunction "1_1") (pintype "passive"))
      (node (ref "R29") (pin "1") (pinfunction "1_1") (pintype "passive"))
      (node (ref "R3") (pin "2") (pinfunction "2_2") (pintype "passive"))
      (node (ref "R30") (pin "1") (pinfunction "1_1") (pintype "passive"))
      (node (ref "R31") (pin "1") (pinfunction "1_1") (pintype "passive"))
      (node (ref "R32") (pin "1") (pinfunction "1_1") (pintype "passive"))
      (node (ref "R33") (pin "1") (pinfunction "1_1") (pintype "passive"))
      (node (ref "R34") (pin "1") (pinfunction "1_1") (pintype "passive"))
      (node (ref "R35") (pin "1") (pinfunction "1_1") (pintype "passive"))
      (node (ref "R36") (pin "1") (pinfunction "1_1") (pintype "passive"))
      (node (ref "R37") (pin "2") (pinfunction "2_2") (pintype "passive"))
      (node (ref "R39") (pin "2") (pinfunction "2_2") (pintype "passive"))
      (node (ref "R41") (pin "2") (pinfunction "2_2") (pintype "passive"))
      (node (ref "R42") (pin "2") (pinfunction "2_2") (pintype "passive"))
      (node (ref "R49") (pin "2") (pinfunction "2_2") (pintype "passive"))
      (node (ref "R5") (pin "2") (pinfunction "2_2") (pintype "passive"))
      (node (ref "R51") (pin "2") (pinfunction "2_2") (pintype "passive"))
      (node (ref "R53") (pin "1") (pinfunction "1_1") (pintype "passive"))
      (node (ref "R54") (pin "1") (pinfunction "1_1") (pintype "passive"))
      (node (ref "R55") (pin "1") (pinfunction "1_1") (pintype "passive"))
      (node (ref "R56") (pin "1") (pinfunction "1_1") (pintype "passive"))
      (node (ref "R60") (pin "2") (pinfunction "2_2") (pintype "passive"))
      (node (ref "R62") (pin "2") (pinfunction "2_2") (pintype "passive"))
      (node (ref "R64") (pin "2") (pinfunction "2_2") (pintype "passive"))
      (node (ref "R65") (pin "1") (pinfunction "1_1") (pintype "passive"))
      (node (ref "R66") (pin "2") (pinfunction "2_2") (pintype "passive"))
      (node (ref "R68") (pin "2") (pinfunction "2_2") (pintype "passive"))
      (node (ref "R7") (pin "2") (pinfunction "2_2") (pintype "passive"))
      (node (ref "R9") (pin "2") (pinfunction "2_2") (pintype "passive"))
      (node (ref "SDCARD_CONNECTOR") (pin "1") (pinfunction "1_1") (pintype "passive"))
      (node (ref "SDCARD_CONNECTOR") (pin "2") (pinfunction "2_2") (pintype "passive"))
      (node (ref "USB-UART_1") (pin "3") (pinfunction "3_3") (pintype "passive"))
    )
    (net (code "261") (name "VDD_5V_GPIO") (class "Default")
      (node (ref "GPIO_0") (pin "11") (pinfunction "11_11") (pintype "passive"))
      (node (ref "GPIO_1") (pin "11") (pinfunction "11_11") (pintype "passive"))
      (node (ref "GPIO_2") (pin "11") (pinfunction "11_11") (pintype "passive"))
      (node (ref "GPIO_3") (pin "11") (pinfunction "11_11") (pintype "passive"))
      (node (ref "Q21") (pin "1") (pinfunction "G_1") (pintype "bidirectional"))
      (node (ref "R69") (pin "1") (pinfunction "1_1") (pintype "passive"))
      (node (ref "VDD") (pin "3") (pinfunction "3_3") (pintype "passive"))
      (node (ref "VDDO") (pin "3") (pinfunction "3_3") (pintype "passive"))
      (node (ref "VDD_3V3") (pin "3") (pinfunction "3_3") (pintype "passive"))
    )
    (net (code "262") (name "VDD_5V_USB") (class "Default")
      (node (ref "Q20") (pin "1") (pinfunction "G_1") (pintype "bidirectional"))
      (node (ref "R67") (pin "1") (pinfunction "1_1") (pintype "passive"))
      (node (ref "USB-UART_2") (pin "2") (pinfunction "2_2") (pintype "passive"))
      (node (ref "VDD") (pin "1") (pinfunction "1_1") (pintype "passive"))
      (node (ref "VDDO") (pin "1") (pinfunction "1_1") (pintype "passive"))
      (node (ref "VDD_3V3") (pin "1") (pinfunction "1_1") (pintype "passive"))
    )
    (net (code "263") (name "unconnected-(FLASH_CONNECTOR-Pad9)") (class "Default")
      (node (ref "FLASH_CONNECTOR") (pin "9") (pinfunction "9_9") (pintype "passive"))
    )
    (net (code "264") (name "unconnected-(FLASH_CONNECTOR-Pad11)") (class "Default")
      (node (ref "FLASH_CONNECTOR") (pin "11") (pinfunction "11_11") (pintype "passive"))
    )
    (net (code "265") (name "unconnected-(GPIO_0-Pad1)") (class "Default")
      (node (ref "GPIO_0") (pin "1") (pinfunction "1_1") (pintype "passive"))
    )
    (net (code "266") (name "unconnected-(GPIO_0-Pad2)") (class "Default")
      (node (ref "GPIO_0") (pin "2") (pinfunction "2_2") (pintype "passive"))
    )
    (net (code "267") (name "unconnected-(GPIO_0-Pad3)") (class "Default")
      (node (ref "GPIO_0") (pin "3") (pinfunction "3_3") (pintype "passive"))
    )
    (net (code "268") (name "unconnected-(GPIO_0-Pad4)") (class "Default")
      (node (ref "GPIO_0") (pin "4") (pinfunction "4_4") (pintype "passive"))
    )
    (net (code "269") (name "unconnected-(GPIO_0-Pad6)") (class "Default")
      (node (ref "GPIO_0") (pin "6") (pinfunction "6_6") (pintype "passive"))
    )
    (net (code "270") (name "unconnected-(GPIO_0-Pad8)") (class "Default")
      (node (ref "GPIO_0") (pin "8") (pinfunction "8_8") (pintype "passive"))
    )
    (net (code "271") (name "unconnected-(GPIO_0-Pad10)") (class "Default")
      (node (ref "GPIO_0") (pin "10") (pinfunction "10_10") (pintype "passive"))
    )
    (net (code "272") (name "unconnected-(GPIO_0-Pad14)") (class "Default")
      (node (ref "GPIO_0") (pin "14") (pinfunction "14_14") (pintype "passive"))
    )
    (net (code "273") (name "unconnected-(GPIO_0-Pad16)") (class "Default")
      (node (ref "GPIO_0") (pin "16") (pinfunction "16_16") (pintype "passive"))
    )
    (net (code "274") (name "unconnected-(GPIO_0-Pad18)") (class "Default")
      (node (ref "GPIO_0") (pin "18") (pinfunction "18_18") (pintype "passive"))
    )
    (net (code "275") (name "unconnected-(GPIO_0-Pad20)") (class "Default")
      (node (ref "GPIO_0") (pin "20") (pinfunction "20_20") (pintype "passive"))
    )
    (net (code "276") (name "unconnected-(GPIO_0-Pad22)") (class "Default")
      (node (ref "GPIO_0") (pin "22") (pinfunction "22_22") (pintype "passive"))
    )
    (net (code "277") (name "unconnected-(GPIO_0-Pad24)") (class "Default")
      (node (ref "GPIO_0") (pin "24") (pinfunction "24_24") (pintype "passive"))
    )
    (net (code "278") (name "unconnected-(GPIO_0-Pad26)") (class "Default")
      (node (ref "GPIO_0") (pin "26") (pinfunction "26_26") (pintype "passive"))
    )
    (net (code "279") (name "unconnected-(GPIO_0-Pad28)") (class "Default")
      (node (ref "GPIO_0") (pin "28") (pinfunction "28_28") (pintype "passive"))
    )
    (net (code "280") (name "unconnected-(GPIO_0-Pad32)") (class "Default")
      (node (ref "GPIO_0") (pin "32") (pinfunction "32_32") (pintype "passive"))
    )
    (net (code "281") (name "unconnected-(GPIO_0-Pad34)") (class "Default")
      (node (ref "GPIO_0") (pin "34") (pinfunction "34_34") (pintype "passive"))
    )
    (net (code "282") (name "unconnected-(GPIO_0-Pad36)") (class "Default")
      (node (ref "GPIO_0") (pin "36") (pinfunction "36_36") (pintype "passive"))
    )
    (net (code "283") (name "unconnected-(GPIO_0-Pad38)") (class "Default")
      (node (ref "GPIO_0") (pin "38") (pinfunction "38_38") (pintype "passive"))
    )
    (net (code "284") (name "unconnected-(GPIO_0-Pad40)") (class "Default")
      (node (ref "GPIO_0") (pin "40") (pinfunction "40_40") (pintype "passive"))
    )
    (net (code "285") (name "unconnected-(GPIO_1-Pad2)") (class "Default")
      (node (ref "GPIO_1") (pin "2") (pinfunction "2_2") (pintype "passive"))
    )
    (net (code "286") (name "unconnected-(GPIO_1-Pad3)") (class "Default")
      (node (ref "GPIO_1") (pin "3") (pinfunction "3_3") (pintype "passive"))
    )
    (net (code "287") (name "unconnected-(GPIO_1-Pad4)") (class "Default")
      (node (ref "GPIO_1") (pin "4") (pinfunction "4_4") (pintype "passive"))
    )
    (net (code "288") (name "unconnected-(GPIO_1-Pad6)") (class "Default")
      (node (ref "GPIO_1") (pin "6") (pinfunction "6_6") (pintype "passive"))
    )
    (net (code "289") (name "unconnected-(GPIO_1-Pad8)") (class "Default")
      (node (ref "GPIO_1") (pin "8") (pinfunction "8_8") (pintype "passive"))
    )
    (net (code "290") (name "unconnected-(GPIO_1-Pad10)") (class "Default")
      (node (ref "GPIO_1") (pin "10") (pinfunction "10_10") (pintype "passive"))
    )
    (net (code "291") (name "unconnected-(GPIO_1-Pad14)") (class "Default")
      (node (ref "GPIO_1") (pin "14") (pinfunction "14_14") (pintype "passive"))
    )
    (net (code "292") (name "unconnected-(GPIO_1-Pad16)") (class "Default")
      (node (ref "GPIO_1") (pin "16") (pinfunction "16_16") (pintype "passive"))
    )
    (net (code "293") (name "unconnected-(GPIO_1-Pad18)") (class "Default")
      (node (ref "GPIO_1") (pin "18") (pinfunction "18_18") (pintype "passive"))
    )
    (net (code "294") (name "unconnected-(GPIO_1-Pad20)") (class "Default")
      (node (ref "GPIO_1") (pin "20") (pinfunction "20_20") (pintype "passive"))
    )
    (net (code "295") (name "unconnected-(GPIO_1-Pad22)") (class "Default")
      (node (ref "GPIO_1") (pin "22") (pinfunction "22_22") (pintype "passive"))
    )
    (net (code "296") (name "unconnected-(GPIO_1-Pad23)") (class "Default")
      (node (ref "GPIO_1") (pin "23") (pinfunction "23_23") (pintype "passive"))
    )
    (net (code "297") (name "unconnected-(GPIO_1-Pad24)") (class "Default")
      (node (ref "GPIO_1") (pin "24") (pinfunction "24_24") (pintype "passive"))
    )
    (net (code "298") (name "unconnected-(GPIO_1-Pad26)") (class "Default")
      (node (ref "GPIO_1") (pin "26") (pinfunction "26_26") (pintype "passive"))
    )
    (net (code "299") (name "unconnected-(GPIO_1-Pad28)") (class "Default")
      (node (ref "GPIO_1") (pin "28") (pinfunction "28_28") (pintype "passive"))
    )
    (net (code "300") (name "unconnected-(GPIO_1-Pad32)") (class "Default")
      (node (ref "GPIO_1") (pin "32") (pinfunction "32_32") (pintype "passive"))
    )
    (net (code "301") (name "unconnected-(GPIO_1-Pad34)") (class "Default")
      (node (ref "GPIO_1") (pin "34") (pinfunction "34_34") (pintype "passive"))
    )
    (net (code "302") (name "unconnected-(GPIO_1-Pad36)") (class "Default")
      (node (ref "GPIO_1") (pin "36") (pinfunction "36_36") (pintype "passive"))
    )
    (net (code "303") (name "unconnected-(GPIO_1-Pad38)") (class "Default")
      (node (ref "GPIO_1") (pin "38") (pinfunction "38_38") (pintype "passive"))
    )
    (net (code "304") (name "unconnected-(GPIO_1-Pad40)") (class "Default")
      (node (ref "GPIO_1") (pin "40") (pinfunction "40_40") (pintype "passive"))
    )
    (net (code "305") (name "unconnected-(GPIO_2-Pad1)") (class "Default")
      (node (ref "GPIO_2") (pin "1") (pinfunction "1_1") (pintype "passive"))
    )
    (net (code "306") (name "unconnected-(GPIO_2-Pad2)") (class "Default")
      (node (ref "GPIO_2") (pin "2") (pinfunction "2_2") (pintype "passive"))
    )
    (net (code "307") (name "unconnected-(GPIO_2-Pad3)") (class "Default")
      (node (ref "GPIO_2") (pin "3") (pinfunction "3_3") (pintype "passive"))
    )
    (net (code "308") (name "unconnected-(GPIO_2-Pad4)") (class "Default")
      (node (ref "GPIO_2") (pin "4") (pinfunction "4_4") (pintype "passive"))
    )
    (net (code "309") (name "unconnected-(GPIO_2-Pad6)") (class "Default")
      (node (ref "GPIO_2") (pin "6") (pinfunction "6_6") (pintype "passive"))
    )
    (net (code "310") (name "unconnected-(GPIO_2-Pad8)") (class "Default")
      (node (ref "GPIO_2") (pin "8") (pinfunction "8_8") (pintype "passive"))
    )
    (net (code "311") (name "unconnected-(GPIO_2-Pad10)") (class "Default")
      (node (ref "GPIO_2") (pin "10") (pinfunction "10_10") (pintype "passive"))
    )
    (net (code "312") (name "unconnected-(GPIO_2-Pad14)") (class "Default")
      (node (ref "GPIO_2") (pin "14") (pinfunction "14_14") (pintype "passive"))
    )
    (net (code "313") (name "unconnected-(GPIO_2-Pad16)") (class "Default")
      (node (ref "GPIO_2") (pin "16") (pinfunction "16_16") (pintype "passive"))
    )
    (net (code "314") (name "unconnected-(GPIO_2-Pad18)") (class "Default")
      (node (ref "GPIO_2") (pin "18") (pinfunction "18_18") (pintype "passive"))
    )
    (net (code "315") (name "unconnected-(GPIO_2-Pad20)") (class "Default")
      (node (ref "GPIO_2") (pin "20") (pinfunction "20_20") (pintype "passive"))
    )
    (net (code "316") (name "unconnected-(GPIO_2-Pad22)") (class "Default")
      (node (ref "GPIO_2") (pin "22") (pinfunction "22_22") (pintype "passive"))
    )
    (net (code "317") (name "unconnected-(GPIO_2-Pad24)") (class "Default")
      (node (ref "GPIO_2") (pin "24") (pinfunction "24_24") (pintype "passive"))
    )
    (net (code "318") (name "unconnected-(GPIO_2-Pad26)") (class "Default")
      (node (ref "GPIO_2") (pin "26") (pinfunction "26_26") (pintype "passive"))
    )
    (net (code "319") (name "unconnected-(GPIO_2-Pad27)") (class "Default")
      (node (ref "GPIO_2") (pin "27") (pinfunction "27_27") (pintype "passive"))
    )
    (net (code "320") (name "unconnected-(GPIO_2-Pad28)") (class "Default")
      (node (ref "GPIO_2") (pin "28") (pinfunction "28_28") (pintype "passive"))
    )
    (net (code "321") (name "unconnected-(GPIO_2-Pad31)") (class "Default")
      (node (ref "GPIO_2") (pin "31") (pinfunction "31_31") (pintype "passive"))
    )
    (net (code "322") (name "unconnected-(GPIO_2-Pad32)") (class "Default")
      (node (ref "GPIO_2") (pin "32") (pinfunction "32_32") (pintype "passive"))
    )
    (net (code "323") (name "unconnected-(GPIO_2-Pad33)") (class "Default")
      (node (ref "GPIO_2") (pin "33") (pinfunction "33_33") (pintype "passive"))
    )
    (net (code "324") (name "unconnected-(GPIO_2-Pad34)") (class "Default")
      (node (ref "GPIO_2") (pin "34") (pinfunction "34_34") (pintype "passive"))
    )
    (net (code "325") (name "unconnected-(GPIO_2-Pad35)") (class "Default")
      (node (ref "GPIO_2") (pin "35") (pinfunction "35_35") (pintype "passive"))
    )
    (net (code "326") (name "unconnected-(GPIO_2-Pad36)") (class "Default")
      (node (ref "GPIO_2") (pin "36") (pinfunction "36_36") (pintype "passive"))
    )
    (net (code "327") (name "unconnected-(GPIO_2-Pad37)") (class "Default")
      (node (ref "GPIO_2") (pin "37") (pinfunction "37_37") (pintype "passive"))
    )
    (net (code "328") (name "unconnected-(GPIO_2-Pad38)") (class "Default")
      (node (ref "GPIO_2") (pin "38") (pinfunction "38_38") (pintype "passive"))
    )
    (net (code "329") (name "unconnected-(GPIO_2-Pad39)") (class "Default")
      (node (ref "GPIO_2") (pin "39") (pinfunction "39_39") (pintype "passive"))
    )
    (net (code "330") (name "unconnected-(GPIO_2-Pad40)") (class "Default")
      (node (ref "GPIO_2") (pin "40") (pinfunction "40_40") (pintype "passive"))
    )
    (net (code "331") (name "unconnected-(GPIO_3-Pad1)") (class "Default")
      (node (ref "GPIO_3") (pin "1") (pinfunction "1_1") (pintype "passive"))
    )
    (net (code "332") (name "unconnected-(GPIO_3-Pad2)") (class "Default")
      (node (ref "GPIO_3") (pin "2") (pinfunction "2_2") (pintype "passive"))
    )
    (net (code "333") (name "unconnected-(GPIO_3-Pad3)") (class "Default")
      (node (ref "GPIO_3") (pin "3") (pinfunction "3_3") (pintype "passive"))
    )
    (net (code "334") (name "unconnected-(GPIO_3-Pad4)") (class "Default")
      (node (ref "GPIO_3") (pin "4") (pinfunction "4_4") (pintype "passive"))
    )
    (net (code "335") (name "unconnected-(GPIO_3-Pad5)") (class "Default")
      (node (ref "GPIO_3") (pin "5") (pinfunction "5_5") (pintype "passive"))
    )
    (net (code "336") (name "unconnected-(GPIO_3-Pad6)") (class "Default")
      (node (ref "GPIO_3") (pin "6") (pinfunction "6_6") (pintype "passive"))
    )
    (net (code "337") (name "unconnected-(GPIO_3-Pad7)") (class "Default")
      (node (ref "GPIO_3") (pin "7") (pinfunction "7_7") (pintype "passive"))
    )
    (net (code "338") (name "unconnected-(GPIO_3-Pad8)") (class "Default")
      (node (ref "GPIO_3") (pin "8") (pinfunction "8_8") (pintype "passive"))
    )
    (net (code "339") (name "unconnected-(GPIO_3-Pad9)") (class "Default")
      (node (ref "GPIO_3") (pin "9") (pinfunction "9_9") (pintype "passive"))
    )
    (net (code "340") (name "unconnected-(GPIO_3-Pad10)") (class "Default")
      (node (ref "GPIO_3") (pin "10") (pinfunction "10_10") (pintype "passive"))
    )
    (net (code "341") (name "unconnected-(GPIO_3-Pad13)") (class "Default")
      (node (ref "GPIO_3") (pin "13") (pinfunction "13_13") (pintype "passive"))
    )
    (net (code "342") (name "unconnected-(GPIO_3-Pad14)") (class "Default")
      (node (ref "GPIO_3") (pin "14") (pinfunction "14_14") (pintype "passive"))
    )
    (net (code "343") (name "unconnected-(GPIO_3-Pad15)") (class "Default")
      (node (ref "GPIO_3") (pin "15") (pinfunction "15_15") (pintype "passive"))
    )
    (net (code "344") (name "unconnected-(GPIO_3-Pad16)") (class "Default")
      (node (ref "GPIO_3") (pin "16") (pinfunction "16_16") (pintype "passive"))
    )
    (net (code "345") (name "unconnected-(GPIO_3-Pad17)") (class "Default")
      (node (ref "GPIO_3") (pin "17") (pinfunction "17_17") (pintype "passive"))
    )
    (net (code "346") (name "unconnected-(GPIO_3-Pad18)") (class "Default")
      (node (ref "GPIO_3") (pin "18") (pinfunction "18_18") (pintype "passive"))
    )
    (net (code "347") (name "unconnected-(GPIO_3-Pad19)") (class "Default")
      (node (ref "GPIO_3") (pin "19") (pinfunction "19_19") (pintype "passive"))
    )
    (net (code "348") (name "unconnected-(GPIO_3-Pad20)") (class "Default")
      (node (ref "GPIO_3") (pin "20") (pinfunction "20_20") (pintype "passive"))
    )
    (net (code "349") (name "unconnected-(GPIO_3-Pad21)") (class "Default")
      (node (ref "GPIO_3") (pin "21") (pinfunction "21_21") (pintype "passive"))
    )
    (net (code "350") (name "unconnected-(GPIO_3-Pad22)") (class "Default")
      (node (ref "GPIO_3") (pin "22") (pinfunction "22_22") (pintype "passive"))
    )
    (net (code "351") (name "unconnected-(GPIO_3-Pad23)") (class "Default")
      (node (ref "GPIO_3") (pin "23") (pinfunction "23_23") (pintype "passive"))
    )
    (net (code "352") (name "unconnected-(GPIO_3-Pad24)") (class "Default")
      (node (ref "GPIO_3") (pin "24") (pinfunction "24_24") (pintype "passive"))
    )
    (net (code "353") (name "unconnected-(GPIO_3-Pad25)") (class "Default")
      (node (ref "GPIO_3") (pin "25") (pinfunction "25_25") (pintype "passive"))
    )
    (net (code "354") (name "unconnected-(GPIO_3-Pad26)") (class "Default")
      (node (ref "GPIO_3") (pin "26") (pinfunction "26_26") (pintype "passive"))
    )
    (net (code "355") (name "unconnected-(GPIO_3-Pad27)") (class "Default")
      (node (ref "GPIO_3") (pin "27") (pinfunction "27_27") (pintype "passive"))
    )
    (net (code "356") (name "unconnected-(GPIO_3-Pad28)") (class "Default")
      (node (ref "GPIO_3") (pin "28") (pinfunction "28_28") (pintype "passive"))
    )
    (net (code "357") (name "unconnected-(GPIO_3-Pad31)") (class "Default")
      (node (ref "GPIO_3") (pin "31") (pinfunction "31_31") (pintype "passive"))
    )
    (net (code "358") (name "unconnected-(GPIO_3-Pad32)") (class "Default")
      (node (ref "GPIO_3") (pin "32") (pinfunction "32_32") (pintype "passive"))
    )
    (net (code "359") (name "unconnected-(GPIO_3-Pad33)") (class "Default")
      (node (ref "GPIO_3") (pin "33") (pinfunction "33_33") (pintype "passive"))
    )
    (net (code "360") (name "unconnected-(GPIO_3-Pad34)") (class "Default")
      (node (ref "GPIO_3") (pin "34") (pinfunction "34_34") (pintype "passive"))
    )
    (net (code "361") (name "unconnected-(GPIO_3-Pad35)") (class "Default")
      (node (ref "GPIO_3") (pin "35") (pinfunction "35_35") (pintype "passive"))
    )
    (net (code "362") (name "unconnected-(GPIO_3-Pad36)") (class "Default")
      (node (ref "GPIO_3") (pin "36") (pinfunction "36_36") (pintype "passive"))
    )
    (net (code "363") (name "unconnected-(GPIO_3-Pad37)") (class "Default")
      (node (ref "GPIO_3") (pin "37") (pinfunction "37_37") (pintype "passive"))
    )
    (net (code "364") (name "unconnected-(GPIO_3-Pad38)") (class "Default")
      (node (ref "GPIO_3") (pin "38") (pinfunction "38_38") (pintype "passive"))
    )
    (net (code "365") (name "unconnected-(GPIO_3-Pad39)") (class "Default")
      (node (ref "GPIO_3") (pin "39") (pinfunction "39_39") (pintype "passive"))
    )
    (net (code "366") (name "unconnected-(GPIO_3-Pad40)") (class "Default")
      (node (ref "GPIO_3") (pin "40") (pinfunction "40_40") (pintype "passive"))
    )
    (net (code "367") (name "unconnected-(IC1-A1-Pad1)") (class "Default")
      (node (ref "IC1") (pin "1") (pinfunction "A1_1") (pintype "bidirectional"))
    )
    (net (code "368") (name "unconnected-(IC1-A6-Pad7)") (class "Default")
      (node (ref "IC1") (pin "7") (pinfunction "A6_7") (pintype "bidirectional"))
    )
    (net (code "369") (name "unconnected-(IC1-A7-Pad8)") (class "Default")
      (node (ref "IC1") (pin "8") (pinfunction "A7_8") (pintype "bidirectional"))
    )
    (net (code "370") (name "unconnected-(IC1-A8-Pad9)") (class "Default")
      (node (ref "IC1") (pin "9") (pinfunction "A8_9") (pintype "bidirectional"))
    )
    (net (code "371") (name "unconnected-(IC1-B1-Pad20)") (class "Default")
      (node (ref "IC1") (pin "20") (pinfunction "B1_20") (pintype "bidirectional"))
    )
    (net (code "372") (name "unconnected-(IC1-B6-Pad14)") (class "Default")
      (node (ref "IC1") (pin "14") (pinfunction "B6_14") (pintype "bidirectional"))
    )
    (net (code "373") (name "unconnected-(IC1-B7-Pad13)") (class "Default")
      (node (ref "IC1") (pin "13") (pinfunction "B7_13") (pintype "bidirectional"))
    )
    (net (code "374") (name "unconnected-(IC1-B8-Pad12)") (class "Default")
      (node (ref "IC1") (pin "12") (pinfunction "B8_12") (pintype "bidirectional"))
    )
    (net (code "375") (name "unconnected-(IC2-A1-Pad1)") (class "Default")
      (node (ref "IC2") (pin "1") (pinfunction "A1_1") (pintype "bidirectional"))
    )
    (net (code "376") (name "unconnected-(IC2-A2-Pad3)") (class "Default")
      (node (ref "IC2") (pin "3") (pinfunction "A2_3") (pintype "bidirectional"))
    )
    (net (code "377") (name "unconnected-(IC2-A5-Pad6)") (class "Default")
      (node (ref "IC2") (pin "6") (pinfunction "A5_6") (pintype "bidirectional"))
    )
    (net (code "378") (name "unconnected-(IC2-A6-Pad7)") (class "Default")
      (node (ref "IC2") (pin "7") (pinfunction "A6_7") (pintype "bidirectional"))
    )
    (net (code "379") (name "unconnected-(IC2-A7-Pad8)") (class "Default")
      (node (ref "IC2") (pin "8") (pinfunction "A7_8") (pintype "bidirectional"))
    )
    (net (code "380") (name "unconnected-(IC2-A8-Pad9)") (class "Default")
      (node (ref "IC2") (pin "9") (pinfunction "A8_9") (pintype "bidirectional"))
    )
    (net (code "381") (name "unconnected-(IC2-B1-Pad20)") (class "Default")
      (node (ref "IC2") (pin "20") (pinfunction "B1_20") (pintype "bidirectional"))
    )
    (net (code "382") (name "unconnected-(IC2-B2-Pad18)") (class "Default")
      (node (ref "IC2") (pin "18") (pinfunction "B2_18") (pintype "bidirectional"))
    )
    (net (code "383") (name "unconnected-(IC2-B5-Pad15)") (class "Default")
      (node (ref "IC2") (pin "15") (pinfunction "B5_15") (pintype "bidirectional"))
    )
    (net (code "384") (name "unconnected-(IC2-B6-Pad14)") (class "Default")
      (node (ref "IC2") (pin "14") (pinfunction "B6_14") (pintype "bidirectional"))
    )
    (net (code "385") (name "unconnected-(IC2-B7-Pad13)") (class "Default")
      (node (ref "IC2") (pin "13") (pinfunction "B7_13") (pintype "bidirectional"))
    )
    (net (code "386") (name "unconnected-(IC2-B8-Pad12)") (class "Default")
      (node (ref "IC2") (pin "12") (pinfunction "B8_12") (pintype "bidirectional"))
    )
    (net (code "387") (name "unconnected-(IC4-A1-Pad1)") (class "Default")
      (node (ref "IC4") (pin "1") (pinfunction "A1_1") (pintype "bidirectional"))
    )
    (net (code "388") (name "unconnected-(IC4-A8-Pad9)") (class "Default")
      (node (ref "IC4") (pin "9") (pinfunction "A8_9") (pintype "bidirectional"))
    )
    (net (code "389") (name "unconnected-(IC4-B1-Pad20)") (class "Default")
      (node (ref "IC4") (pin "20") (pinfunction "B1_20") (pintype "bidirectional"))
    )
    (net (code "390") (name "unconnected-(IC4-B8-Pad12)") (class "Default")
      (node (ref "IC4") (pin "12") (pinfunction "B8_12") (pintype "bidirectional"))
    )
    (net (code "391") (name "unconnected-(IC6-A1-Pad1)") (class "Default")
      (node (ref "IC6") (pin "1") (pinfunction "A1_1") (pintype "bidirectional"))
    )
    (net (code "392") (name "unconnected-(IC6-A6-Pad7)") (class "Default")
      (node (ref "IC6") (pin "7") (pinfunction "A6_7") (pintype "bidirectional"))
    )
    (net (code "393") (name "unconnected-(IC6-A7-Pad8)") (class "Default")
      (node (ref "IC6") (pin "8") (pinfunction "A7_8") (pintype "bidirectional"))
    )
    (net (code "394") (name "unconnected-(IC6-A8-Pad9)") (class "Default")
      (node (ref "IC6") (pin "9") (pinfunction "A8_9") (pintype "bidirectional"))
    )
    (net (code "395") (name "unconnected-(IC6-B1-Pad20)") (class "Default")
      (node (ref "IC6") (pin "20") (pinfunction "B1_20") (pintype "bidirectional"))
    )
    (net (code "396") (name "unconnected-(IC6-B6-Pad14)") (class "Default")
      (node (ref "IC6") (pin "14") (pinfunction "B6_14") (pintype "bidirectional"))
    )
    (net (code "397") (name "unconnected-(IC6-B7-Pad13)") (class "Default")
      (node (ref "IC6") (pin "13") (pinfunction "B7_13") (pintype "bidirectional"))
    )
    (net (code "398") (name "unconnected-(IC6-B8-Pad12)") (class "Default")
      (node (ref "IC6") (pin "12") (pinfunction "B8_12") (pintype "bidirectional"))
    )
    (net (code "399") (name "unconnected-(JTAG_CONNECTOR-Pad3)") (class "Default")
      (node (ref "JTAG_CONNECTOR") (pin "3") (pinfunction "3_3") (pintype "passive"))
    )
    (net (code "400") (name "unconnected-(JTAG_CONNECTOR-Pad11)") (class "Default")
      (node (ref "JTAG_CONNECTOR") (pin "11") (pinfunction "11_11") (pintype "passive"))
    )
    (net (code "401") (name "unconnected-(JTAG_CONNECTOR-Pad15)") (class "Default")
      (node (ref "JTAG_CONNECTOR") (pin "15") (pinfunction "15_15") (pintype "passive"))
    )
    (net (code "402") (name "unconnected-(JTAG_CONNECTOR-Pad17)") (class "Default")
      (node (ref "JTAG_CONNECTOR") (pin "17") (pinfunction "17_17") (pintype "passive"))
    )
    (net (code "403") (name "unconnected-(JTAG_CONNECTOR-Pad19)") (class "Default")
      (node (ref "JTAG_CONNECTOR") (pin "19") (pinfunction "19_19") (pintype "passive"))
    )
    (net (code "404") (name "unconnected-(SDCARD_CONNECTOR-Pad5)") (class "Default")
      (node (ref "SDCARD_CONNECTOR") (pin "5") (pinfunction "5_5") (pintype "passive"))
    )
    (net (code "405") (name "unconnected-(SDCARD_CONNECTOR-Pad7)") (class "Default")
      (node (ref "SDCARD_CONNECTOR") (pin "7") (pinfunction "7_7") (pintype "passive"))
    )
    (net (code "406") (name "unconnected-(SDCARD_CONNECTOR-Pad9)") (class "Default")
      (node (ref "SDCARD_CONNECTOR") (pin "9") (pinfunction "9_9") (pintype "passive"))
    )
    (net (code "407") (name "unconnected-(SDCARD_CONNECTOR-Pad11)") (class "Default")
      (node (ref "SDCARD_CONNECTOR") (pin "11") (pinfunction "11_11") (pintype "passive"))
    )
    (net (code "408") (name "unconnected-(U$1-Pad2)") (class "Default")
      (node (ref "U$1") (pin "2") (pinfunction "2_2") (pintype "bidirectional"))
    )
    (net (code "409") (name "unconnected-(U$1-Pad41)") (class "Default")
      (node (ref "U$1") (pin "41") (pinfunction "41_41") (pintype "bidirectional"))
    )
    (net (code "410") (name "unconnected-(U$2-Pad2)") (class "Default")
      (node (ref "U$2") (pin "2") (pinfunction "2_2") (pintype "bidirectional"))
    )
    (net (code "411") (name "unconnected-(U$2-Pad41)") (class "Default")
      (node (ref "U$2") (pin "41") (pinfunction "41_41") (pintype "bidirectional"))
    )
    (net (code "412") (name "unconnected-(U$3-Pad2)") (class "Default")
      (node (ref "U$3") (pin "2") (pinfunction "2_2") (pintype "bidirectional"))
    )
    (net (code "413") (name "unconnected-(U$3-Pad41)") (class "Default")
      (node (ref "U$3") (pin "41") (pinfunction "41_41") (pintype "bidirectional"))
    )
    (net (code "414") (name "unconnected-(U$4-Pad2)") (class "Default")
      (node (ref "U$4") (pin "2") (pinfunction "2_2") (pintype "bidirectional"))
    )
    (net (code "415") (name "unconnected-(U$4-Pad41)") (class "Default")
      (node (ref "U$4") (pin "41") (pinfunction "41_41") (pintype "bidirectional"))
    )
    (net (code "416") (name "unconnected-(USB-UART_2-Pad1)") (class "Default")
      (node (ref "USB-UART_2") (pin "1") (pinfunction "1_1") (pintype "passive"))
    )
    (net (code "417") (name "unconnected-(USB-UART_2-Pad3)") (class "Default")
      (node (ref "USB-UART_2") (pin "3") (pinfunction "3_3") (pintype "passive"))
    )
    (net (code "418") (name "unconnected-(USB-UART_2-Pad4)") (class "Default")
      (node (ref "USB-UART_2") (pin "4") (pinfunction "4_4") (pintype "passive"))
    )
  )
)
